# ProDoc_TC264_V2_0_2025-08-21.net
KiCad netlist of a schematic drawn in EasyEDA Pro
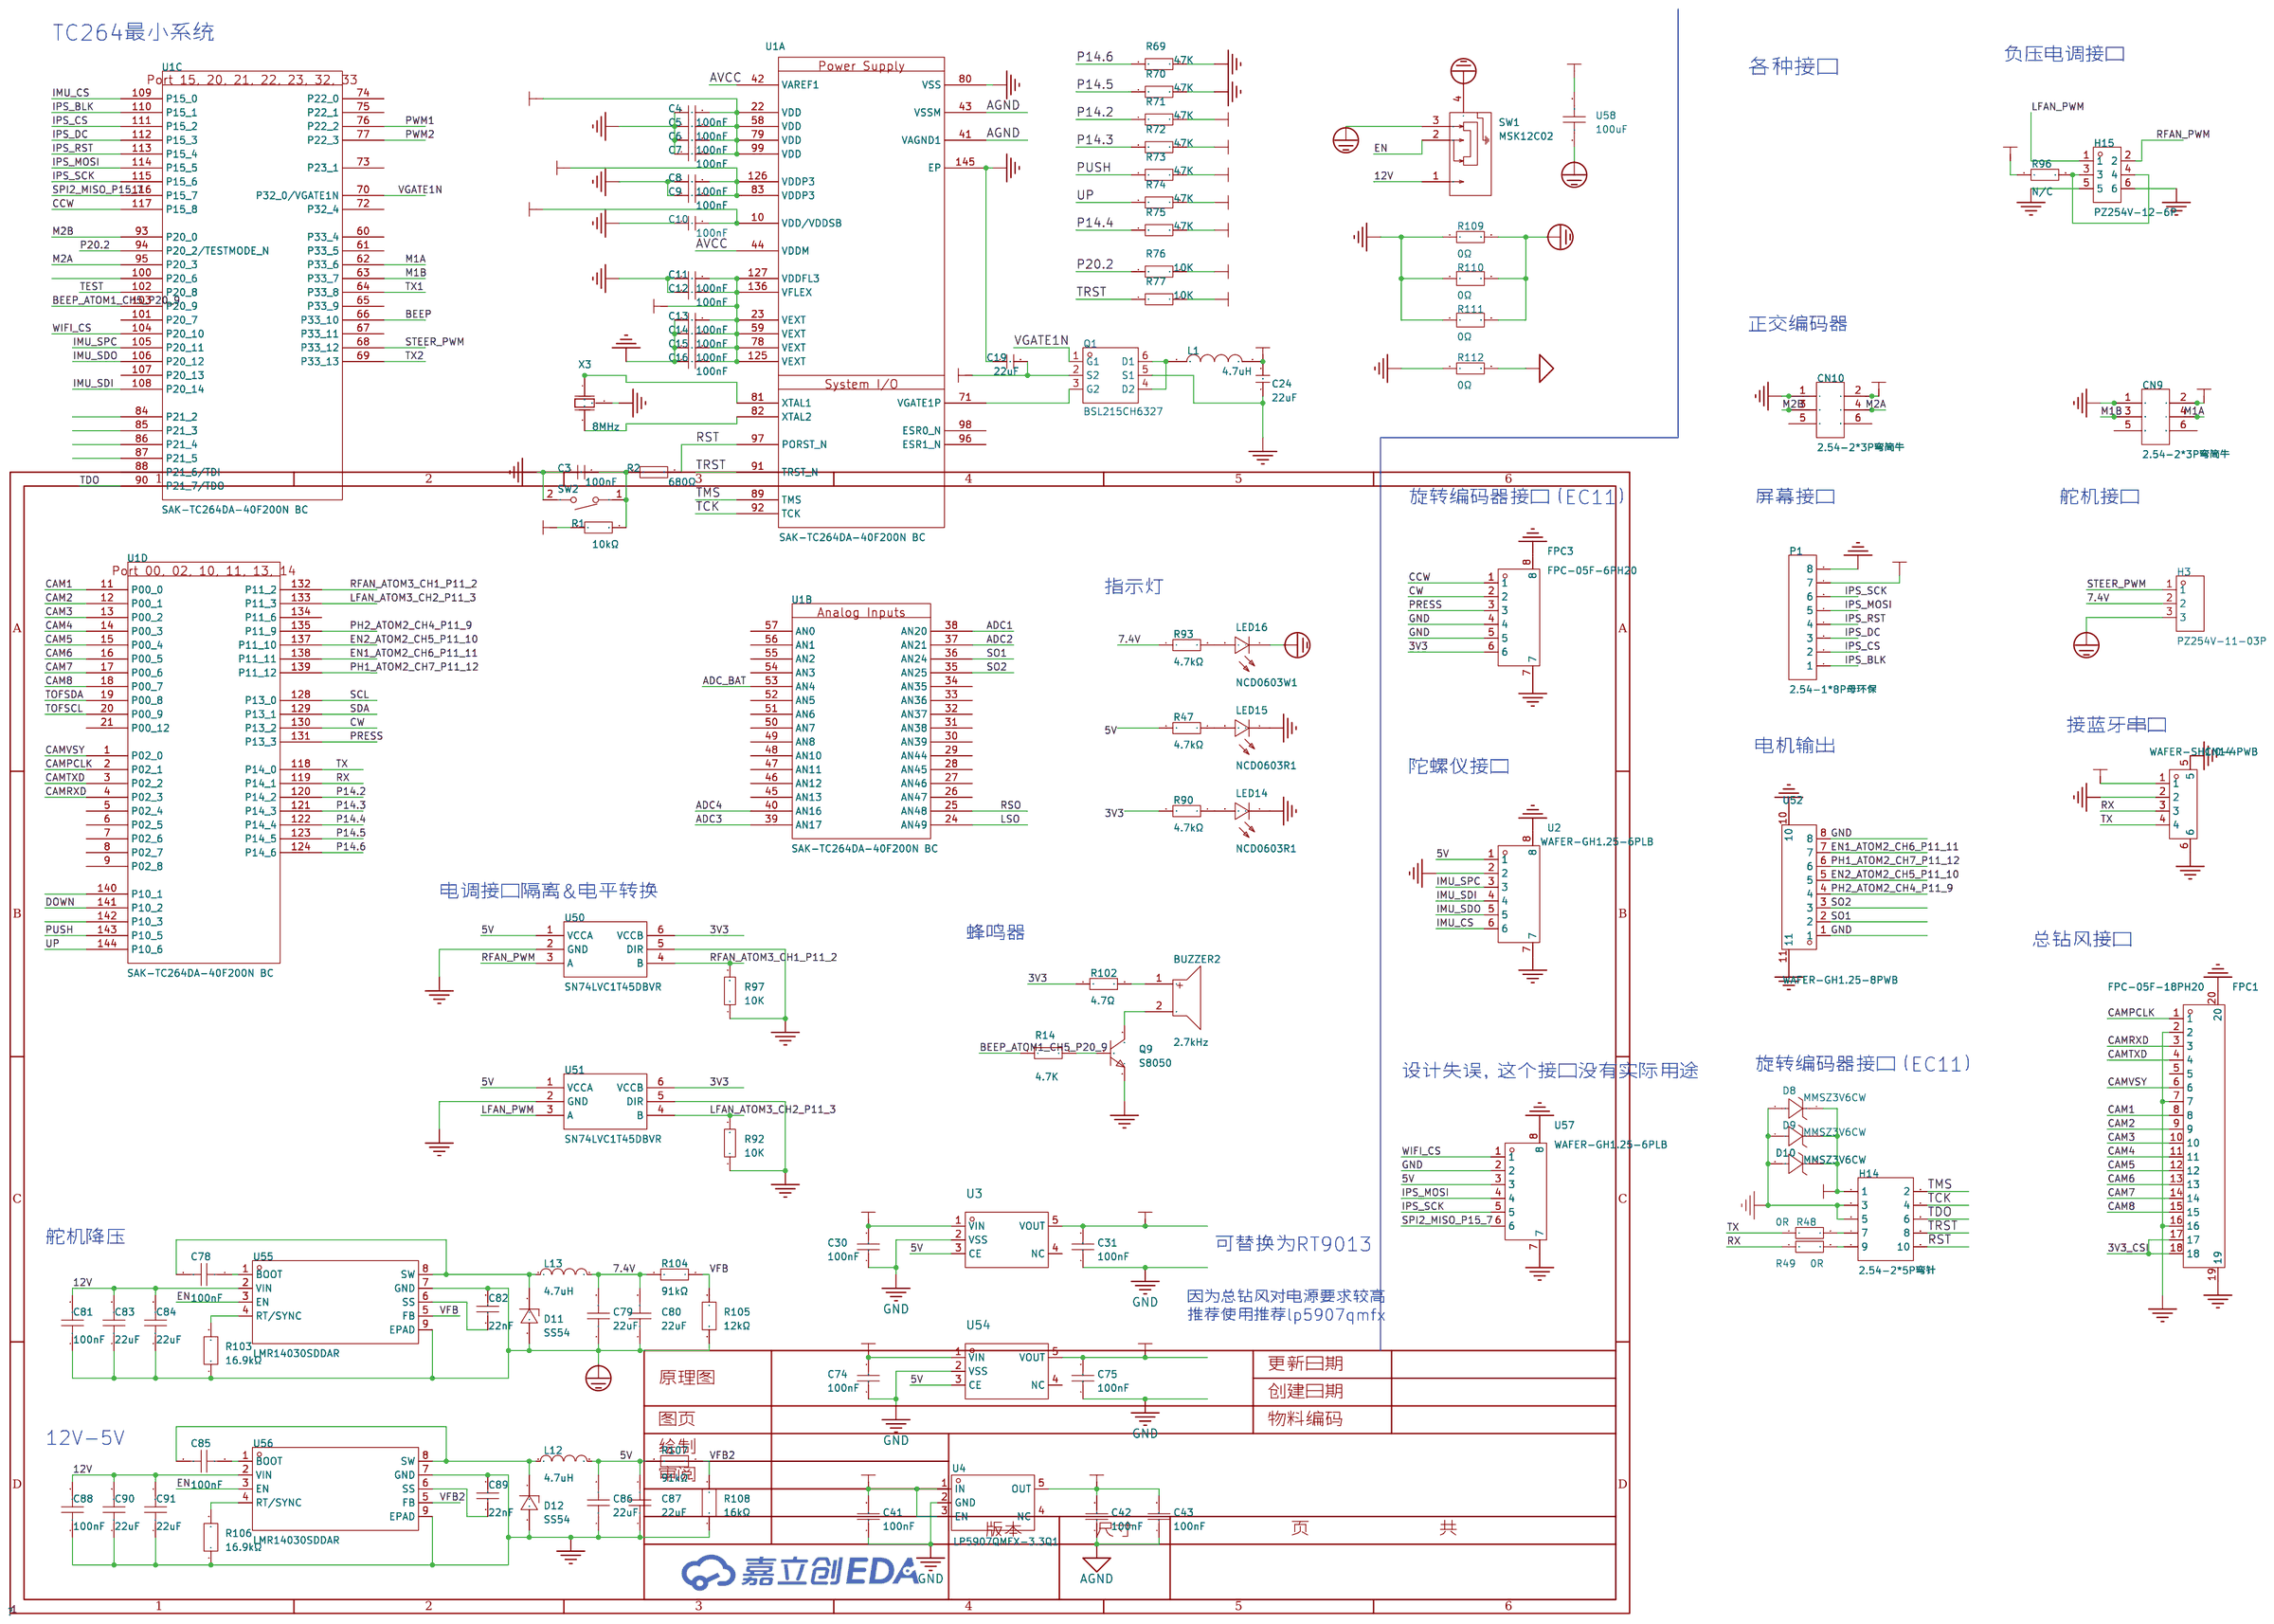
[diagram p0: schematic sheet]

(export (version "E")
  (design (tool "Eeschema 10.0.6"))
  (components
    (comp (ref "BUZZER2")
      (value "2.7kHz")
      (fields (field (name "Manufacturer Part") "QMB-09B-03") (field (name "Manufacturer") "华能"))
      (libsource (lib "easyedapro") (part "QMB-09B-03"))
    )
    (comp (ref "C3")
      (value "100nF")
      (fields (field (name "Manufacturer Part") "0603B104K500NT") (field (name "Manufacturer") "FH(风华)"))
      (libsource (lib "easyedapro") (part "c"))
    )
    (comp (ref "C4")
      (value "100nF")
      (fields (field (name "Manufacturer Part") "0603B104K500NT") (field (name "Manufacturer") "FH(风华)"))
      (libsource (lib "easyedapro") (part "c"))
    )
    (comp (ref "C5")
      (value "100nF")
      (fields (field (name "Manufacturer Part") "0603B104K500NT") (field (name "Manufacturer") "FH(风华)"))
      (libsource (lib "easyedapro") (part "c"))
    )
    (comp (ref "C6")
      (value "100nF")
      (fields (field (name "Manufacturer Part") "0603B104K500NT") (field (name "Manufacturer") "FH(风华)"))
      (libsource (lib "easyedapro") (part "c"))
    )
    (comp (ref "C7")
      (value "100nF")
      (fields (field (name "Manufacturer Part") "0603B104K500NT") (field (name "Manufacturer") "FH(风华)"))
      (libsource (lib "easyedapro") (part "c"))
    )
    (comp (ref "C8")
      (value "100nF")
      (fields (field (name "Manufacturer Part") "0603B104K500NT") (field (name "Manufacturer") "FH(风华)"))
      (libsource (lib "easyedapro") (part "c"))
    )
    (comp (ref "C9")
      (value "100nF")
      (fields (field (name "Manufacturer Part") "0603B104K500NT") (field (name "Manufacturer") "FH(风华)"))
      (libsource (lib "easyedapro") (part "c"))
    )
    (comp (ref "C10")
      (value "100nF")
      (fields (field (name "Manufacturer Part") "0603B104K500NT") (field (name "Manufacturer") "FH(风华)"))
      (libsource (lib "easyedapro") (part "c"))
    )
    (comp (ref "C11")
      (value "100nF")
      (fields (field (name "Manufacturer Part") "0603B104K500NT") (field (name "Manufacturer") "FH(风华)"))
      (libsource (lib "easyedapro") (part "c"))
    )
    (comp (ref "C12")
      (value "100nF")
      (fields (field (name "Manufacturer Part") "0603B104K500NT") (field (name "Manufacturer") "FH(风华)"))
      (libsource (lib "easyedapro") (part "c"))
    )
    (comp (ref "C13")
      (value "100nF")
      (fields (field (name "Manufacturer Part") "0603B104K500NT") (field (name "Manufacturer") "FH(风华)"))
      (libsource (lib "easyedapro") (part "c"))
    )
    (comp (ref "C14")
      (value "100nF")
      (fields (field (name "Manufacturer Part") "0603B104K500NT") (field (name "Manufacturer") "FH(风华)"))
      (libsource (lib "easyedapro") (part "c"))
    )
    (comp (ref "C15")
      (value "100nF")
      (fields (field (name "Manufacturer Part") "0603B104K500NT") (field (name "Manufacturer") "FH(风华)"))
      (libsource (lib "easyedapro") (part "c"))
    )
    (comp (ref "C16")
      (value "100nF")
      (fields (field (name "Manufacturer Part") "0603B104K500NT") (field (name "Manufacturer") "FH(风华)"))
      (libsource (lib "easyedapro") (part "c"))
    )
    (comp (ref "C19")
      (value "22uF")
      (fields
        (field (name "Manufacturer Part") "CL21A226MAQNNNE")
        (field (name "Manufacturer") "SAMSUNG(三星)")
      )
      (libsource (lib "easyedapro") (part "c"))
    )
    (comp (ref "C24")
      (value "22uF")
      (fields
        (field (name "Manufacturer Part") "CL21A226MAQNNNE")
        (field (name "Manufacturer") "SAMSUNG(三星)")
      )
      (libsource (lib "easyedapro") (part "c"))
    )
    (comp (ref "C30")
      (value "100nF")
      (fields (field (name "Manufacturer Part") "0603B104K500NT") (field (name "Manufacturer") "FH(风华)"))
      (libsource (lib "easyedapro") (part "C0603_S"))
    )
    (comp (ref "C31")
      (value "100nF")
      (fields (field (name "Manufacturer Part") "0603B104K500NT") (field (name "Manufacturer") "FH(风华)"))
      (libsource (lib "easyedapro") (part "C0603_S"))
    )
    (comp (ref "C41")
      (value "100nF")
      (fields (field (name "Manufacturer Part") "0603B104K500NT") (field (name "Manufacturer") "FH(风华)"))
      (libsource (lib "easyedapro") (part "C0603_S"))
    )
    (comp (ref "C42")
      (value "100nF")
      (fields (field (name "Manufacturer Part") "0603B104K500NT") (field (name "Manufacturer") "FH(风华)"))
      (libsource (lib "easyedapro") (part "C0603_S"))
    )
    (comp (ref "C43")
      (value "100nF")
      (fields (field (name "Manufacturer Part") "0603B104K500NT") (field (name "Manufacturer") "FH(风华)"))
      (libsource (lib "easyedapro") (part "C0603_S"))
    )
    (comp (ref "C74")
      (value "100nF")
      (fields (field (name "Manufacturer Part") "0603B104K500NT") (field (name "Manufacturer") "FH(风华)"))
      (libsource (lib "easyedapro") (part "C0603_S"))
    )
    (comp (ref "C75")
      (value "100nF")
      (fields (field (name "Manufacturer Part") "0603B104K500NT") (field (name "Manufacturer") "FH(风华)"))
      (libsource (lib "easyedapro") (part "C0603_S"))
    )
    (comp (ref "C78")
      (value "100nF")
      (footprint "easyedapro:C0603")
      (description "容值:100nF;精度:±10%;额定电压:50V;材质(温度系数):X7R;")
      (fields
        (field (name "Manufacturer Part") "CGA0603X7R104K500JT")
        (field (name "Manufacturer") "HRE(芯声)")
      )
      (libsource (lib "easyedapro") (part "CGA0603X7R104K500JT"))
    )
    (comp (ref "C79")
      (value "22uF")
      (footprint "easyedapro:C0805")
      (description "容值:22uF;精度:±20%;额定电压:35V;材质(温度系数):X5R;")
      (fields
        (field (name "Manufacturer Part") "CGA0805X5R226M350MT")
        (field (name "Manufacturer") "HRE(芯声)")
      )
      (libsource (lib "easyedapro") (part "CGA0805X5R226M350MT"))
    )
    (comp (ref "C80")
      (value "22uF")
      (footprint "easyedapro:C0805")
      (description "容值:22uF;精度:±20%;额定电压:35V;材质(温度系数):X5R;")
      (fields
        (field (name "Manufacturer Part") "CGA0805X5R226M350MT")
        (field (name "Manufacturer") "HRE(芯声)")
      )
      (libsource (lib "easyedapro") (part "CGA0805X5R226M350MT"))
    )
    (comp (ref "C81")
      (value "100nF")
      (footprint "easyedapro:C0603")
      (description "容值:100nF;精度:±10%;额定电压:50V;材质(温度系数):X7R;")
      (fields
        (field (name "Manufacturer Part") "CGA0603X7R104K500JT")
        (field (name "Manufacturer") "HRE(芯声)")
      )
      (libsource (lib "easyedapro") (part "CGA0603X7R104K500JT"))
    )
    (comp (ref "C82")
      (value "22nF")
      (footprint "easyedapro:C0603")
      (description "容值:22nF;精度:±10%;额定电压:50V;材质(温度系数):X7R;")
      (fields
        (field (name "Manufacturer Part") "CL10B223KB8NNNC")
        (field (name "Manufacturer") "SAMSUNG(三星)")
      )
      (libsource (lib "easyedapro") (part "CL10B223KB8NNNC"))
    )
    (comp (ref "C83")
      (value "22uF")
      (footprint "easyedapro:C0805")
      (description "容值:22uF;精度:±20%;额定电压:35V;材质(温度系数):X5R;")
      (fields
        (field (name "Manufacturer Part") "CGA0805X5R226M350MT")
        (field (name "Manufacturer") "HRE(芯声)")
      )
      (libsource (lib "easyedapro") (part "CGA0805X5R226M350MT"))
    )
    (comp (ref "C84")
      (value "22uF")
      (footprint "easyedapro:C0805")
      (description "容值:22uF;精度:±20%;额定电压:35V;材质(温度系数):X5R;")
      (fields
        (field (name "Manufacturer Part") "CGA0805X5R226M350MT")
        (field (name "Manufacturer") "HRE(芯声)")
      )
      (libsource (lib "easyedapro") (part "CGA0805X5R226M350MT"))
    )
    (comp (ref "C85")
      (value "100nF")
      (footprint "easyedapro:C0603")
      (description "容值:100nF;精度:±10%;额定电压:50V;材质(温度系数):X7R;")
      (fields
        (field (name "Manufacturer Part") "CGA0603X7R104K500JT")
        (field (name "Manufacturer") "HRE(芯声)")
      )
      (libsource (lib "easyedapro") (part "CGA0603X7R104K500JT"))
    )
    (comp (ref "C86")
      (value "22uF")
      (footprint "easyedapro:C0805")
      (description "容值:22uF;精度:±20%;额定电压:35V;材质(温度系数):X5R;")
      (fields
        (field (name "Manufacturer Part") "CGA0805X5R226M350MT")
        (field (name "Manufacturer") "HRE(芯声)")
      )
      (libsource (lib "easyedapro") (part "CGA0805X5R226M350MT"))
    )
    (comp (ref "C87")
      (value "22uF")
      (footprint "easyedapro:C0805")
      (description "容值:22uF;精度:±20%;额定电压:35V;材质(温度系数):X5R;")
      (fields
        (field (name "Manufacturer Part") "CGA0805X5R226M350MT")
        (field (name "Manufacturer") "HRE(芯声)")
      )
      (libsource (lib "easyedapro") (part "CGA0805X5R226M350MT"))
    )
    (comp (ref "C88")
      (value "100nF")
      (footprint "easyedapro:C0603")
      (description "容值:100nF;精度:±10%;额定电压:50V;材质(温度系数):X7R;")
      (fields
        (field (name "Manufacturer Part") "CGA0603X7R104K500JT")
        (field (name "Manufacturer") "HRE(芯声)")
      )
      (libsource (lib "easyedapro") (part "CGA0603X7R104K500JT"))
    )
    (comp (ref "C89")
      (value "22nF")
      (footprint "easyedapro:C0603")
      (description "容值:22nF;精度:±10%;额定电压:50V;材质(温度系数):X7R;")
      (fields
        (field (name "Manufacturer Part") "CL10B223KB8NNNC")
        (field (name "Manufacturer") "SAMSUNG(三星)")
      )
      (libsource (lib "easyedapro") (part "CL10B223KB8NNNC"))
    )
    (comp (ref "C90")
      (value "22uF")
      (footprint "easyedapro:C0805")
      (description "容值:22uF;精度:±20%;额定电压:35V;材质(温度系数):X5R;")
      (fields
        (field (name "Manufacturer Part") "CGA0805X5R226M350MT")
        (field (name "Manufacturer") "HRE(芯声)")
      )
      (libsource (lib "easyedapro") (part "CGA0805X5R226M350MT"))
    )
    (comp (ref "C91")
      (value "22uF")
      (footprint "easyedapro:C0805")
      (description "容值:22uF;精度:±20%;额定电压:35V;材质(温度系数):X5R;")
      (fields
        (field (name "Manufacturer Part") "CGA0805X5R226M350MT")
        (field (name "Manufacturer") "HRE(芯声)")
      )
      (libsource (lib "easyedapro") (part "CGA0805X5R226M350MT"))
    )
    (comp (ref "CN9")
      (value "2.54-2*3P弯简牛")
      (footprint "easyedapro:IDC-TH_6P-P2.54-H-R2-C3-S2.54")
      (description "连接器类型:简牛座;间距:2.54mm;结构:2x3P;封装形式:弯插;行距:2.54mm;排数:2;每排PIN数:3;触头材质:-;触头镀层:-;")
      (fields (field (name "Manufacturer") "BOOMELE(博穆精密)"))
      (libsource (lib "easyedapro") (part "2.54mm 2*3P bend IDC Box"))
    )
    (comp (ref "CN10")
      (value "2.54-2*3P弯简牛")
      (footprint "easyedapro:IDC-TH_6P-P2.54-H-R2-C3-S2.54")
      (description "连接器类型:简牛座;间距:2.54mm;结构:2x3P;封装形式:弯插;行距:2.54mm;排数:2;每排PIN数:3;触头材质:-;触头镀层:-;")
      (fields (field (name "Manufacturer") "BOOMELE(博穆精密)"))
      (libsource (lib "easyedapro") (part "2.54mm 2*3P bend IDC Box"))
    )
    (comp (ref "CN14")
      (value "WAFER-SH1.0-4PWB")
      (footprint "easyedapro:CONN-SMD_4P-P1.00_WAFER-SH1.0-4PWB")
      (fields (field (name "Manufacturer") "XUNPU(讯普)"))
      (libsource (lib "easyedapro") (part "WAFER-SH1.0-4PWB"))
    )
    (comp (ref "D8")
      (value "MMSZ3V6CW")
      (footprint "easyedapro:SOD-123_L2.7-W1.6-LS3.7-RD-1")
      (description "二极管配置:独立式;稳压值(标称值):3.6V;稳压值(范围):3.4V~3.8V;功率(Pd):500mW;")
      (fields (field (name "Manufacturer") "YONGYUTAI(永裕泰)"))
      (libsource (lib "easyedapro") (part "MMSZ3V6CW_C2922768"))
    )
    (comp (ref "D9")
      (value "MMSZ3V6CW")
      (footprint "easyedapro:SOD-123_L2.7-W1.6-LS3.7-RD-1")
      (description "二极管配置:独立式;稳压值(标称值):3.6V;稳压值(范围):3.4V~3.8V;功率(Pd):500mW;")
      (fields (field (name "Manufacturer") "YONGYUTAI(永裕泰)"))
      (libsource (lib "easyedapro") (part "MMSZ3V6CW_C2922768"))
    )
    (comp (ref "D10")
      (value "MMSZ3V6CW")
      (footprint "easyedapro:SOD-123_L2.7-W1.6-LS3.7-RD-1")
      (description "二极管配置:独立式;稳压值(标称值):3.6V;稳压值(范围):3.4V~3.8V;功率(Pd):500mW;")
      (fields (field (name "Manufacturer") "YONGYUTAI(永裕泰)"))
      (libsource (lib "easyedapro") (part "MMSZ3V6CW_C2922768"))
    )
    (comp (ref "D11")
      (value "SS54")
      (footprint "easyedapro:SMA_L4.3-W2.6-LS5.0-FD")
      (description "二极管配置:独立式;正向压降(Vf):550mV@5.0A;直流反向耐压(Vr):40V;整流电流:5A;")
      (fields (field (name "Manufacturer") "宏迦橙"))
      (libsource (lib "easyedapro") (part "SS54_C7420369"))
    )
    (comp (ref "D12")
      (value "SS54")
      (footprint "easyedapro:SMA_L4.3-W2.6-LS5.0-FD")
      (description "二极管配置:独立式;正向压降(Vf):550mV@5.0A;直流反向耐压(Vr):40V;整流电流:5A;")
      (fields (field (name "Manufacturer") "宏迦橙"))
      (libsource (lib "easyedapro") (part "SS54_C7420369"))
    )
    (comp (ref "FPC1")
      (value "FPC-05F-18PH20")
      (footprint "easyedapro:FPC-SMD_18P-P0.50_FPC-05F-18PH20")
      (description "锁定特性:翻盖式;触点类型:下接;触点数量:18P;间距:0.5mm;安装类型:卧贴;工作温度范围:-25°C~+85°C;")
      (fields (field (name "Manufacturer") "XUNPU(讯普)"))
      (libsource (lib "easyedapro") (part "FPC-05F-18PH20"))
    )
    (comp (ref "FPC3")
      (value "FPC-05F-6PH20")
      (footprint "easyedapro:FPC-SMD_6P-P0.50_XUNPU_FPC-05F-6PH20")
      (description "锁定特性:翻盖式;触点类型:下接;触点数量:6P;间距:0.5mm;安装类型:卧贴;工作温度范围:-25°C~+85°C;")
      (fields (field (name "Manufacturer") "XUNPU(讯普)"))
      (libsource (lib "easyedapro") (part "FPC-05F-6PH20"))
    )
    (comp (ref "H3")
      (value "PZ254V-11-03P")
      (fields (field (name "Manufacturer") "XFCN(兴飞)"))
      (libsource (lib "easyedapro") (part "PZ254V-11-03P_C2937625"))
    )
    (comp (ref "H14")
      (value "2.54-2*5P弯针")
      (footprint "easyedapro:HDR-TH_10P-P2.54-H-M-R2-C5-S2.54-W12.9")
      (fields (field (name "Manufacturer") "BOOMELE(博穆精密)"))
      (libsource (lib "easyedapro") (part "2*5P header"))
    )
    (comp (ref "H15")
      (value "PZ254V-12-6P")
      (footprint "easyedapro:HDR-TH_6P-P2.54-V-M-R2-C3-S2.54")
      (fields (field (name "Manufacturer") "XFCN(兴飞)"))
      (libsource (lib "easyedapro") (part "PZ254V-12-6P"))
    )
    (comp (ref "L1")
      (value "4.7uH")
      (fields (field (name "Manufacturer Part") "LQM21PL4R7MGCD") (field (name "Manufacturer") "muRata(村田)"))
      (libsource (lib "easyedapro") (part "l"))
    )
    (comp (ref "L12")
      (value "4.7uH")
      (footprint "easyedapro:IND-SMD_L7.0-W6.6")
      (description "电感值:4.7uH;精度:±20%;额定电流:6A;饱和电流(Isat):9A;类型:一体成型电感;")
      (fields (field (name "Manufacturer Part") "FXL0630-4R7-M") (field (name "Manufacturer") "cjiang(长江微电)"))
      (libsource (lib "easyedapro") (part "FXL0630-4R7-M"))
    )
    (comp (ref "L13")
      (value "4.7uH")
      (footprint "easyedapro:IND-SMD_L7.0-W6.6")
      (description "电感值:4.7uH;精度:±20%;额定电流:6A;饱和电流(Isat):9A;类型:一体成型电感;")
      (fields (field (name "Manufacturer Part") "FXL0630-4R7-M") (field (name "Manufacturer") "cjiang(长江微电)"))
      (libsource (lib "easyedapro") (part "FXL0630-4R7-M"))
    )
    (comp (ref "LED14")
      (value "NCD0603R1")
      (footprint "easyedapro:LED0603-RD_RED")
      (fields (field (name "Manufacturer") "国星光电"))
      (libsource (lib "easyedapro") (part "FC-DA1608HRK-620D"))
    )
    (comp (ref "LED15")
      (value "NCD0603R1")
      (footprint "easyedapro:LED0603-RD_RED")
      (fields (field (name "Manufacturer") "国星光电"))
      (libsource (lib "easyedapro") (part "FC-DA1608HRK-620D"))
    )
    (comp (ref "LED16")
      (value "NCD0603W1")
      (footprint "easyedapro:LED0603-RD")
      (fields (field (name "Manufacturer") "国星光电"))
      (libsource (lib "easyedapro") (part "NCD0603W1"))
    )
    (comp (ref "P1")
      (value "2.54-1*8P母环保")
      (footprint "easyedapro:HDR-TH_8P-P2.54-V-F-1")
      (description "插孔结构:1x8P;间距:2.54mm;行距:-;安装类型:直插;排数:单排;总孔位数:8P;塑高:-;触头材质:-;触头镀层:-;")
      (fields (field (name "Manufacturer") "BOOMELE(博穆精密)"))
      (libsource (lib "easyedapro") (part "Header-Female-2.54_1x8"))
    )
    (comp (ref "Q1")
      (value "BSL215CH6327")
      (fields (field (name "Manufacturer") "Infineon(英飞凌)"))
      (libsource (lib "easyedapro") (part "bsl215ch6327xtsa1"))
    )
    (comp (ref "Q9")
      (value "S8050")
      (footprint "easyedapro:SOT-23-3_L2.9-W1.3-P1.90-LS2.4-BR")
      (description "晶体管类型:NPN;集电极电流(Ic):500mA;集射极击穿电压(Vceo):25V;功率(Pd):300mW;")
      (fields (field (name "Manufacturer") "YONGYUTAI(永裕泰)"))
      (libsource (lib "easyedapro") (part "S8050_C2891804"))
    )
    (comp (ref "R1")
      (value "10kΩ")
      (fields
        (field (name "Manufacturer Part") "0603WAF1002T5E")
        (field (name "Manufacturer") "UNI-ROYAL(厚声)")
      )
      (libsource (lib "easyedapro") (part "r"))
    )
    (comp (ref "R2")
      (value "680Ω")
      (fields
        (field (name "Manufacturer Part") "0603WAF6800T5E")
        (field (name "Manufacturer") "UNI-ROYAL(厚声)")
      )
      (libsource (lib "easyedapro") (part "r"))
    )
    (comp (ref "R14") (value "4.7K") (libsource (lib "easyedapro") (part "电阻")))
    (comp (ref "R47")
      (value "4.7kΩ")
      (footprint "easyedapro:R0603")
      (description "电阻类型:厚膜电阻;阻值:4.7kΩ;精度:±1%;功率:100mW;最大工作电压:75V;温度系数:±100ppm/°C;")
      (fields (field (name "Manufacturer Part") "RC0603FR-074K7L") (field (name "Manufacturer") "YAGEO(国巨)"))
      (libsource (lib "easyedapro") (part "RC0603FR-074K7L"))
    )
    (comp (ref "R48") (value "0R") (libsource (lib "easyedapro") (part "电阻")))
    (comp (ref "R49") (value "0R") (libsource (lib "easyedapro") (part "电阻")))
    (comp (ref "R69") (value "47K") (libsource (lib "easyedapro") (part "电阻")))
    (comp (ref "R70") (value "47K") (libsource (lib "easyedapro") (part "电阻")))
    (comp (ref "R71") (value "47K") (libsource (lib "easyedapro") (part "电阻")))
    (comp (ref "R72") (value "47K") (libsource (lib "easyedapro") (part "电阻")))
    (comp (ref "R73") (value "47K") (libsource (lib "easyedapro") (part "电阻")))
    (comp (ref "R74") (value "47K") (libsource (lib "easyedapro") (part "电阻")))
    (comp (ref "R75") (value "47K") (libsource (lib "easyedapro") (part "电阻")))
    (comp (ref "R76") (value "10K") (libsource (lib "easyedapro") (part "电阻")))
    (comp (ref "R77") (value "10K") (libsource (lib "easyedapro") (part "电阻")))
    (comp (ref "R90")
      (value "4.7kΩ")
      (footprint "easyedapro:R0603")
      (description "电阻类型:厚膜电阻;阻值:4.7kΩ;精度:±1%;功率:100mW;最大工作电压:75V;温度系数:±100ppm/°C;")
      (fields (field (name "Manufacturer Part") "RC0603FR-074K7L") (field (name "Manufacturer") "YAGEO(国巨)"))
      (libsource (lib "easyedapro") (part "RC0603FR-074K7L"))
    )
    (comp (ref "R92") (value "10K") (footprint "easyedapro:R0603") (libsource (lib "easyedapro") (part "电阻")))
    (comp (ref "R93")
      (value "4.7kΩ")
      (footprint "easyedapro:R0603")
      (description "电阻类型:厚膜电阻;阻值:6.8kΩ;精度:±1%;功率:100mW;最大工作电压:75V;温度系数:±100ppm/°C;")
      (fields
        (field (name "Manufacturer Part") "0603WAF6801T5E")
        (field (name "Manufacturer") "UNI-ROYAL(厚声)")
      )
      (libsource (lib "easyedapro") (part "0603WAF6801T5E"))
    )
    (comp (ref "R96")
      (value "N/C")
      (footprint "easyedapro:R0603")
      (description "电阻类型:厚膜电阻;阻值:0Ω;精度:±1%;功率:100mW;最大工作电压:75V;")
      (fields
        (field (name "Manufacturer Part") "0603WAF0000T5E")
        (field (name "Manufacturer") "UNI-ROYAL(厚声)")
      )
      (libsource (lib "easyedapro") (part "0603WAF0000T5E"))
    )
    (comp (ref "R97") (value "10K") (footprint "easyedapro:R0603") (libsource (lib "easyedapro") (part "电阻")))
    (comp (ref "R102")
      (value "4.7Ω")
      (footprint "easyedapro:R0603")
      (description "电阻类型:厚膜电阻;阻值:100Ω;精度:±1%;功率:100mW;最大工作电压:75V;温度系数:±200ppm/°C;")
      (fields
        (field (name "Manufacturer Part") "0603WAF1000T5E")
        (field (name "Manufacturer") "UNI-ROYAL(厚声)")
      )
      (libsource (lib "easyedapro") (part "0603WAF1000T5E"))
    )
    (comp (ref "R103")
      (value "16.9kΩ")
      (footprint "easyedapro:R0603")
      (description "电阻类型:薄膜电阻;阻值:16.9kΩ;精度:±0.1%;功率:100mW;温度系数:±25ppm/°C;")
      (fields (field (name "Manufacturer Part") "RT0603BRD0716K9L") (field (name "Manufacturer") "YAGEO(国巨)"))
      (libsource (lib "easyedapro") (part "RT0603BRD0716K9L"))
    )
    (comp (ref "R104")
      (value "91kΩ")
      (footprint "easyedapro:R0603")
      (description "电阻类型:厚膜电阻;阻值:100kΩ;精度:±1%;功率:100mW;最大工作电压:75V;温度系数:±100ppm/°C;")
      (fields
        (field (name "Manufacturer Part") "0603WAF1003T5E")
        (field (name "Manufacturer") "UNI-ROYAL(厚声)")
      )
      (libsource (lib "easyedapro") (part "0603WAF1003T5E"))
    )
    (comp (ref "R105")
      (value "12kΩ")
      (footprint "easyedapro:R0603")
      (description "电阻类型:薄膜电阻;阻值:17.8kΩ;精度:±0.1%;功率:100mW;最大工作电压:75V;温度系数:±25ppm/°C;")
      (fields (field (name "Manufacturer Part") "RT0603BRD0717K8L") (field (name "Manufacturer") "YAGEO(国巨)"))
      (libsource (lib "easyedapro") (part "RT0603BRD0717K8L"))
    )
    (comp (ref "R106")
      (value "16.9kΩ")
      (footprint "easyedapro:R0603")
      (description "电阻类型:薄膜电阻;阻值:16.9kΩ;精度:±0.1%;功率:100mW;温度系数:±25ppm/°C;")
      (fields (field (name "Manufacturer Part") "RT0603BRD0716K9L") (field (name "Manufacturer") "YAGEO(国巨)"))
      (libsource (lib "easyedapro") (part "RT0603BRD0716K9L"))
    )
    (comp (ref "R107")
      (value "91kΩ")
      (footprint "easyedapro:R0603")
      (description "电阻类型:厚膜电阻;阻值:100kΩ;精度:±1%;功率:100mW;最大工作电压:75V;温度系数:±100ppm/°C;")
      (fields
        (field (name "Manufacturer Part") "0603WAF1003T5E")
        (field (name "Manufacturer") "UNI-ROYAL(厚声)")
      )
      (libsource (lib "easyedapro") (part "0603WAF1003T5E"))
    )
    (comp (ref "R108")
      (value "16kΩ")
      (footprint "easyedapro:R0603")
      (description "电阻类型:薄膜电阻;阻值:17.8kΩ;精度:±0.1%;功率:100mW;最大工作电压:75V;温度系数:±25ppm/°C;")
      (fields (field (name "Manufacturer Part") "RT0603BRD0717K8L") (field (name "Manufacturer") "YAGEO(国巨)"))
      (libsource (lib "easyedapro") (part "RT0603BRD0717K8L"))
    )
    (comp (ref "R109")
      (value "0Ω")
      (footprint "easyedapro:R1206")
      (description "电阻类型:厚膜电阻;阻值:0Ω;精度:±1%;功率:250mW;最大工作电压:200V;温度系数:±800ppm/°C;")
      (fields
        (field (name "Manufacturer Part") "1206W4F0000T5E")
        (field (name "Manufacturer") "UNI-ROYAL(厚声)")
      )
      (libsource (lib "easyedapro") (part "1206W4F0000T5E"))
    )
    (comp (ref "R110")
      (value "0Ω")
      (footprint "easyedapro:R1206")
      (description "电阻类型:厚膜电阻;阻值:0Ω;精度:±5%;功率:250mW;最大工作电压:200V;")
      (fields (field (name "Manufacturer Part") "FRC1206P000 TS") (field (name "Manufacturer") "FOJAN(富捷)"))
      (libsource (lib "easyedapro") (part "FRC1206P000 TS"))
    )
    (comp (ref "R111")
      (value "0Ω")
      (footprint "easyedapro:R1206")
      (description "电阻类型:厚膜电阻;阻值:0Ω;精度:±5%;功率:250mW;最大工作电压:200V;")
      (fields (field (name "Manufacturer Part") "FRC1206P000 TS") (field (name "Manufacturer") "FOJAN(富捷)"))
      (libsource (lib "easyedapro") (part "FRC1206P000 TS"))
    )
    (comp (ref "R112")
      (value "0Ω")
      (footprint "easyedapro:R0603")
      (description "电阻类型:厚膜电阻;阻值:0Ω;精度:±1%;功率:100mW;最大工作电压:75V;")
      (fields
        (field (name "Manufacturer Part") "0603WAF0000T5E")
        (field (name "Manufacturer") "UNI-ROYAL(厚声)")
      )
      (libsource (lib "easyedapro") (part "0603WAF0000T5E"))
    )
    (comp (ref "SW1")
      (value "MSK12C02")
      (footprint "easyedapro:SW-TH_MSK12C02")
      (description "电路结构:单刀双掷;安装方式:卧贴;开关颜色:-;额定电流(DC):50mA;额定电压(DC):12V;额定电流(AC):-;额定电压(AC):-;机械寿命:1万次;")
      (fields (field (name "Manufacturer") "SHOU HAN(首韩)"))
      (libsource (lib "easyedapro") (part "MSK12C02"))
    )
    (comp (ref "SW2")
      (value "TS-1063S-B3D4")
      (footprint "easyedapro:KEY-SMD_L3.0-W2.5-LS4.0_TS-1603S")
      (description "电路结构:单刀单掷;安装方式:-;按钮形状:方形按钮;带灯:-;作用力:250gf@±30gf;")
      (fields (field (name "Manufacturer") "Yuandi(元迪)"))
      (libsource (lib "easyedapro") (part "TS-1063S-B3D4"))
    )
    (comp (ref "U1")
      (value "SAK-TC264DA-40F200N BC")
      (description "32-Bit Single-Chip Microcontroller BC-Step")
      (libsource (lib "easyedapro") (part "sak-tc264da-40f200n bc"))
    )
    (comp (ref "U2")
      (value "WAFER-GH1.25-6PLB")
      (footprint "easyedapro:CONN-SMD_6P-P1.25_XUNPU_WAFER-GH1.25-6PLB")
      (fields (field (name "Manufacturer") "XUNPU(讯普)"))
      (libsource (lib "easyedapro") (part "WAFER-GH1.25-6PLB"))
    )
    (comp (ref "U3") (value "XC6210B332MR") (libsource (lib "easyedapro") (part "XC6210B332MR")))
    (comp (ref "U4")
      (value "LP5907QMFX-3.3Q1")
      (fields (field (name "Manufacturer") "TI(德州仪器)"))
      (libsource (lib "easyedapro") (part "LP5907QMFX-3.3Q1"))
    )
    (comp (ref "U50")
      (value "SN74LVC1T45DBVR")
      (footprint "easyedapro:SOT-23-6_L2.9-W1.6-P0.95-LS2.8-BR")
      (description "数据速率:420Mbps;电压(VCCA):1.65V~5.5V;电压(VCCB):1.65V~5.5V;电路数:1;每个电路通道数:1;")
      (fields (field (name "Manufacturer") "TI(德州仪器)"))
      (libsource (lib "easyedapro") (part "SN74LVC1T45DBVR"))
    )
    (comp (ref "U51")
      (value "SN74LVC1T45DBVR")
      (footprint "easyedapro:SOT-23-6_L2.9-W1.6-P0.95-LS2.8-BR")
      (description "数据速率:420Mbps;电压(VCCA):1.65V~5.5V;电压(VCCB):1.65V~5.5V;电路数:1;每个电路通道数:1;")
      (fields (field (name "Manufacturer") "TI(德州仪器)"))
      (libsource (lib "easyedapro") (part "SN74LVC1T45DBVR"))
    )
    (comp (ref "U52")
      (value "WAFER-GH1.25-8PWB")
      (footprint "easyedapro:CONN-SMD_8P-P1.25_XUNPU-WAFER-GH1.25-8PWB")
      (description "插针结构:1x8P;间距:1.25mm;安装方式:卧贴;参考系列:GH;总PIN数:8P;排数:1;每排PIN数:8;额定电流:1A;工作温度范围:-25°C~+85°C;")
      (fields (field (name "Manufacturer") "XUNPU(讯普)"))
      (libsource (lib "easyedapro") (part "WAFER-GH1.25-8PWB"))
    )
    (comp (ref "U54") (value "XC6210B332MR") (libsource (lib "easyedapro") (part "XC6210B332MR")))
    (comp (ref "U55")
      (value "LMR14030SDDAR")
      (footprint "easyedapro:SO-8_L4.9-W3.9-P1.27-LS6.0-BL-EP")
      (description "功能类型:降压型;输出类型:可调;输入电压:4V~40V;输出电压:800mV~28V;输出电流(最大值):3.5A;")
      (fields (field (name "Manufacturer") "TI(德州仪器)"))
      (libsource (lib "easyedapro") (part "LMR14030SDDAR"))
    )
    (comp (ref "U56")
      (value "LMR14030SDDAR")
      (footprint "easyedapro:SO-8_L4.9-W3.9-P1.27-LS6.0-BL-EP")
      (description "功能类型:降压型;输出类型:可调;输入电压:4V~40V;输出电压:800mV~28V;输出电流(最大值):3.5A;")
      (fields (field (name "Manufacturer") "TI(德州仪器)"))
      (libsource (lib "easyedapro") (part "LMR14030SDDAR"))
    )
    (comp (ref "U57")
      (value "WAFER-GH1.25-6PLB")
      (footprint "easyedapro:CONN-SMD_6P-P1.25_XUNPU_WAFER-GH1.25-6PLB")
      (fields (field (name "Manufacturer") "XUNPU(讯普)"))
      (libsource (lib "easyedapro") (part "WAFER-GH1.25-6PLB"))
    )
    (comp (ref "U58")
      (value "100uF")
      (footprint "easyedapro:C1210")
      (description "容值:100uF;精度:±20%;额定电压:16V;材质(温度系数):X5R;")
      (fields
        (field (name "Manufacturer Part") "HGC1210R5107M160NSVK")
        (field (name "Manufacturer") "Chinocera(华瓷)")
      )
      (libsource (lib "easyedapro") (part "HGC1210R5107M160NSVK"))
    )
    (comp (ref "X3")
      (value "8MHz")
      (footprint "easyedapro:OSC-SMD_3P-L3.2-W1.3-P1.20-L")
      (description "频率:8MHz;内置负载电容:33pF;谐振阻抗:40Ω;")
      (fields
        (field (name "Manufacturer Part") "CSTNE8M00GH5C000R0")
        (field (name "Manufacturer") "muRata(村田)")
      )
      (libsource (lib "easyedapro") (part "CSTNE8M00GH5C000R0"))
    )
  )
  (nets
    (net (code "1") (name "/7.4V") (class "Default")
      (node (ref "C79") (pin "2") (pinfunction "2_2") (pintype "unspecified"))
      (node (ref "C80") (pin "2") (pinfunction "2_2") (pintype "unspecified"))
      (node (ref "H3") (pin "2") (pinfunction "2_2") (pintype "unspecified"))
      (node (ref "L13") (pin "2") (pinfunction "2_2") (pintype "unspecified"))
      (node (ref "R104") (pin "2") (pinfunction "2_2") (pintype "input"))
      (node (ref "R93") (pin "1") (pinfunction "1_1") (pintype "input"))
    )
    (net (code "2") (name "/ADC1") (class "Default")
      (node (ref "U1") (pin "38") (pinfunction "AN20_38") (pintype "input"))
    )
    (net (code "3") (name "/ADC2") (class "Default")
      (node (ref "U1") (pin "37") (pinfunction "AN21_37") (pintype "input"))
    )
    (net (code "4") (name "/ADC3") (class "Default")
      (node (ref "U1") (pin "39") (pinfunction "AN17_39") (pintype "input"))
    )
    (net (code "5") (name "/ADC4") (class "Default")
      (node (ref "U1") (pin "40") (pinfunction "AN16_40") (pintype "input"))
    )
    (net (code "6") (name "/ADC_BAT") (class "Default")
      (node (ref "U1") (pin "53") (pinfunction "AN4_53") (pintype "input"))
    )
    (net (code "7") (name "/BEEP") (class "Default")
      (node (ref "U1") (pin "66") (pinfunction "P33_10_66") (pintype "bidirectional"))
    )
    (net (code "8") (name "/BEEP_ATOM1_CH5_P20_9") (class "Default")
      (node (ref "R14") (pin "1") (pinfunction "1_1") (pintype "input"))
      (node (ref "U1") (pin "103") (pinfunction "P20_9_103") (pintype "bidirectional"))
    )
    (net (code "9") (name "/CAM1") (class "Default")
      (node (ref "FPC1") (pin "8") (pinfunction "8_8") (pintype "unspecified"))
      (node (ref "U1") (pin "11") (pinfunction "P00_0_11") (pintype "bidirectional"))
    )
    (net (code "10") (name "/CAM2") (class "Default")
      (node (ref "FPC1") (pin "9") (pinfunction "9_9") (pintype "unspecified"))
      (node (ref "U1") (pin "12") (pinfunction "P00_1_12") (pintype "bidirectional"))
    )
    (net (code "11") (name "/CAM3") (class "Default")
      (node (ref "FPC1") (pin "10") (pinfunction "10_10") (pintype "unspecified"))
      (node (ref "U1") (pin "13") (pinfunction "P00_2_13") (pintype "bidirectional"))
    )
    (net (code "12") (name "/CAM4") (class "Default")
      (node (ref "FPC1") (pin "11") (pinfunction "11_11") (pintype "unspecified"))
      (node (ref "U1") (pin "14") (pinfunction "P00_3_14") (pintype "bidirectional"))
    )
    (net (code "13") (name "/CAM5") (class "Default")
      (node (ref "FPC1") (pin "12") (pinfunction "12_12") (pintype "unspecified"))
      (node (ref "U1") (pin "15") (pinfunction "P00_4_15") (pintype "bidirectional"))
    )
    (net (code "14") (name "/CAM6") (class "Default")
      (node (ref "FPC1") (pin "13") (pinfunction "13_13") (pintype "unspecified"))
      (node (ref "U1") (pin "16") (pinfunction "P00_5_16") (pintype "bidirectional"))
    )
    (net (code "15") (name "/CAM7") (class "Default")
      (node (ref "FPC1") (pin "14") (pinfunction "14_14") (pintype "unspecified"))
      (node (ref "U1") (pin "17") (pinfunction "P00_6_17") (pintype "bidirectional"))
    )
    (net (code "16") (name "/CAM8") (class "Default")
      (node (ref "FPC1") (pin "15") (pinfunction "15_15") (pintype "unspecified"))
      (node (ref "U1") (pin "18") (pinfunction "P00_7_18") (pintype "bidirectional"))
    )
    (net (code "17") (name "/CAMPCLK") (class "Default")
      (node (ref "FPC1") (pin "1") (pinfunction "1_1") (pintype "unspecified"))
      (node (ref "U1") (pin "2") (pinfunction "P02_1_2") (pintype "bidirectional"))
    )
    (net (code "18") (name "/CAMRXD") (class "Default")
      (node (ref "FPC1") (pin "3") (pinfunction "3_3") (pintype "unspecified"))
      (node (ref "U1") (pin "4") (pinfunction "P02_3_4") (pintype "bidirectional"))
    )
    (net (code "19") (name "/CAMTXD") (class "Default")
      (node (ref "FPC1") (pin "4") (pinfunction "4_4") (pintype "unspecified"))
      (node (ref "U1") (pin "3") (pinfunction "P02_2_3") (pintype "bidirectional"))
    )
    (net (code "20") (name "/CAMVSY") (class "Default")
      (node (ref "FPC1") (pin "6") (pinfunction "6_6") (pintype "unspecified"))
      (node (ref "U1") (pin "1") (pinfunction "P02_0_1") (pintype "bidirectional"))
    )
    (net (code "21") (name "/CCW") (class "Default")
      (node (ref "FPC3") (pin "1") (pinfunction "1_1") (pintype "unspecified"))
      (node (ref "U1") (pin "117") (pinfunction "P15_8_117") (pintype "bidirectional"))
    )
    (net (code "22") (name "/CW") (class "Default")
      (node (ref "FPC3") (pin "2") (pinfunction "2_2") (pintype "unspecified"))
      (node (ref "U1") (pin "130") (pinfunction "P13_2_130") (pintype "bidirectional"))
    )
    (net (code "23") (name "/DOWN") (class "Default")
      (node (ref "U1") (pin "141") (pinfunction "P10_2_141") (pintype "bidirectional"))
    )
    (net (code "24") (name "/EN") (class "Default")
      (node (ref "SW1") (pin "2") (pinfunction "2_2") (pintype "unspecified"))
      (node (ref "U55") (pin "3") (pinfunction "EN_3") (pintype "unspecified"))
      (node (ref "U56") (pin "3") (pinfunction "EN_3") (pintype "unspecified"))
    )
    (net (code "25") (name "/EN1_ATOM2_CH6_P11_11") (class "Default")
      (node (ref "U1") (pin "138") (pinfunction "P11_11_138") (pintype "bidirectional"))
      (node (ref "U52") (pin "7") (pinfunction "7_7") (pintype "unspecified"))
    )
    (net (code "26") (name "/EN2_ATOM2_CH5_P11_10") (class "Default")
      (node (ref "U1") (pin "137") (pinfunction "P11_10_137") (pintype "bidirectional"))
      (node (ref "U52") (pin "5") (pinfunction "5_5") (pintype "unspecified"))
    )
    (net (code "27") (name "/IMU_CS") (class "Default")
      (node (ref "U1") (pin "109") (pinfunction "P15_0_109") (pintype "bidirectional"))
      (node (ref "U2") (pin "6") (pinfunction "6_6") (pintype "unspecified"))
    )
    (net (code "28") (name "/IMU_SDI") (class "Default")
      (node (ref "U1") (pin "108") (pinfunction "P20_14_108") (pintype "bidirectional"))
      (node (ref "U2") (pin "4") (pinfunction "4_4") (pintype "unspecified"))
    )
    (net (code "29") (name "/IMU_SDO") (class "Default")
      (node (ref "U1") (pin "106") (pinfunction "P20_12_106") (pintype "bidirectional"))
      (node (ref "U2") (pin "5") (pinfunction "5_5") (pintype "unspecified"))
    )
    (net (code "30") (name "/IMU_SPC") (class "Default")
      (node (ref "U1") (pin "105") (pinfunction "P20_11_105") (pintype "bidirectional"))
      (node (ref "U2") (pin "3") (pinfunction "3_3") (pintype "unspecified"))
    )
    (net (code "31") (name "/IPS_BLK") (class "Default")
      (node (ref "P1") (pin "1") (pinfunction "1_1") (pintype "input"))
      (node (ref "U1") (pin "110") (pinfunction "P15_1_110") (pintype "bidirectional"))
    )
    (net (code "32") (name "/IPS_CS") (class "Default")
      (node (ref "P1") (pin "2") (pinfunction "2_2") (pintype "input"))
      (node (ref "U1") (pin "111") (pinfunction "P15_2_111") (pintype "bidirectional"))
    )
    (net (code "33") (name "/IPS_DC") (class "Default")
      (node (ref "P1") (pin "3") (pinfunction "3_3") (pintype "input"))
      (node (ref "U1") (pin "112") (pinfunction "P15_3_112") (pintype "bidirectional"))
    )
    (net (code "34") (name "/IPS_MOSI") (class "Default")
      (node (ref "P1") (pin "5") (pinfunction "5_5") (pintype "input"))
      (node (ref "U1") (pin "114") (pinfunction "P15_5_114") (pintype "bidirectional"))
      (node (ref "U57") (pin "4") (pinfunction "4_4") (pintype "unspecified"))
    )
    (net (code "35") (name "/IPS_RST") (class "Default")
      (node (ref "P1") (pin "4") (pinfunction "4_4") (pintype "input"))
      (node (ref "U1") (pin "113") (pinfunction "P15_4_113") (pintype "bidirectional"))
    )
    (net (code "36") (name "/IPS_SCK") (class "Default")
      (node (ref "P1") (pin "6") (pinfunction "6_6") (pintype "input"))
      (node (ref "U1") (pin "115") (pinfunction "P15_6_115") (pintype "bidirectional"))
      (node (ref "U57") (pin "5") (pinfunction "5_5") (pintype "unspecified"))
    )
    (net (code "37") (name "/LFAN_ATOM3_CH2_P11_3") (class "Default")
      (node (ref "R92") (pin "2") (pinfunction "2_2") (pintype "input"))
      (node (ref "U1") (pin "133") (pinfunction "P11_3_133") (pintype "bidirectional"))
      (node (ref "U51") (pin "4") (pinfunction "B_4") (pintype "unspecified"))
    )
    (net (code "38") (name "/LFAN_PWM") (class "Default")
      (node (ref "H15") (pin "1") (pinfunction "1_1") (pintype "unspecified"))
      (node (ref "U51") (pin "3") (pinfunction "A_3") (pintype "unspecified"))
    )
    (net (code "39") (name "/LSO") (class "Default")
      (node (ref "U1") (pin "24") (pinfunction "AN49_24") (pintype "input"))
    )
    (net (code "40") (name "/M1A") (class "Default")
      (node (ref "CN9") (pin "4") (pinfunction "4_4") (pintype "unspecified"))
      (node (ref "U1") (pin "62") (pinfunction "P33_6_62") (pintype "bidirectional"))
    )
    (net (code "41") (name "/M1B") (class "Default")
      (node (ref "CN9") (pin "3") (pinfunction "3_3") (pintype "unspecified"))
      (node (ref "U1") (pin "63") (pinfunction "P33_7_63") (pintype "bidirectional"))
    )
    (net (code "42") (name "/M2A") (class "Default")
      (node (ref "CN10") (pin "4") (pinfunction "4_4") (pintype "unspecified"))
      (node (ref "U1") (pin "95") (pinfunction "P20_3_95") (pintype "bidirectional"))
    )
    (net (code "43") (name "/M2B") (class "Default")
      (node (ref "CN10") (pin "3") (pinfunction "3_3") (pintype "unspecified"))
      (node (ref "U1") (pin "93") (pinfunction "P20_0_93") (pintype "bidirectional"))
    )
    (net (code "44") (name "/P14.2") (class "Default")
      (node (ref "R71") (pin "1") (pinfunction "1_1") (pintype "input"))
      (node (ref "U1") (pin "120") (pinfunction "P14_2_120") (pintype "bidirectional"))
    )
    (net (code "45") (name "/P14.3") (class "Default")
      (node (ref "R72") (pin "1") (pinfunction "1_1") (pintype "input"))
      (node (ref "U1") (pin "121") (pinfunction "P14_3_121") (pintype "bidirectional"))
    )
    (net (code "46") (name "/P14.4") (class "Default")
      (node (ref "R75") (pin "1") (pinfunction "1_1") (pintype "input"))
      (node (ref "U1") (pin "122") (pinfunction "P14_4_122") (pintype "bidirectional"))
    )
    (net (code "47") (name "/P14.5") (class "Default")
      (node (ref "R70") (pin "1") (pinfunction "1_1") (pintype "input"))
      (node (ref "U1") (pin "123") (pinfunction "P14_5_123") (pintype "bidirectional"))
    )
    (net (code "48") (name "/P14.6") (class "Default")
      (node (ref "R69") (pin "1") (pinfunction "1_1") (pintype "input"))
      (node (ref "U1") (pin "124") (pinfunction "P14_6_124") (pintype "bidirectional"))
    )
    (net (code "49") (name "/P20.2") (class "Default")
      (node (ref "R76") (pin "1") (pinfunction "1_1") (pintype "input"))
      (node (ref "U1") (pin "94") (pinfunction "P20_2/TESTMODE_N_94") (pintype "bidirectional"))
    )
    (net (code "50") (name "/PH1_ATOM2_CH7_P11_12") (class "Default")
      (node (ref "U1") (pin "139") (pinfunction "P11_12_139") (pintype "bidirectional"))
      (node (ref "U52") (pin "6") (pinfunction "6_6") (pintype "unspecified"))
    )
    (net (code "51") (name "/PH2_ATOM2_CH4_P11_9") (class "Default")
      (node (ref "U1") (pin "135") (pinfunction "P11_9_135") (pintype "bidirectional"))
      (node (ref "U52") (pin "4") (pinfunction "4_4") (pintype "unspecified"))
    )
    (net (code "52") (name "/PRESS") (class "Default")
      (node (ref "FPC3") (pin "3") (pinfunction "3_3") (pintype "unspecified"))
      (node (ref "U1") (pin "131") (pinfunction "P13_3_131") (pintype "bidirectional"))
    )
    (net (code "53") (name "/PUSH") (class "Default")
      (node (ref "R73") (pin "1") (pinfunction "1_1") (pintype "input"))
      (node (ref "U1") (pin "143") (pinfunction "P10_5_143") (pintype "bidirectional"))
    )
    (net (code "54") (name "/PWM1") (class "Default")
      (node (ref "U1") (pin "76") (pinfunction "P22_2_76") (pintype "bidirectional"))
    )
    (net (code "55") (name "/PWM2") (class "Default")
      (node (ref "U1") (pin "77") (pinfunction "P22_3_77") (pintype "bidirectional"))
    )
    (net (code "56") (name "/RFAN_ATOM3_CH1_P11_2") (class "Default")
      (node (ref "R97") (pin "2") (pinfunction "2_2") (pintype "input"))
      (node (ref "U1") (pin "132") (pinfunction "P11_2_132") (pintype "bidirectional"))
      (node (ref "U50") (pin "4") (pinfunction "B_4") (pintype "unspecified"))
    )
    (net (code "57") (name "/RFAN_PWM") (class "Default")
      (node (ref "H15") (pin "2") (pinfunction "2_2") (pintype "unspecified"))
      (node (ref "U50") (pin "3") (pinfunction "A_3") (pintype "unspecified"))
    )
    (net (code "58") (name "/RSO") (class "Default")
      (node (ref "U1") (pin "25") (pinfunction "AN48_25") (pintype "input"))
    )
    (net (code "59") (name "/RST") (class "Default")
      (node (ref "H14") (pin "10") (pinfunction "10_10") (pintype "input"))
      (node (ref "R2") (pin "2") (pinfunction "2_2") (pintype "input"))
      (node (ref "U1") (pin "97") (pinfunction "PORST_N_97") (pintype "input"))
    )
    (net (code "60") (name "/RX") (class "Default")
      (node (ref "CN14") (pin "3") (pinfunction "3_3") (pintype "unspecified"))
      (node (ref "R49") (pin "1") (pinfunction "1_1") (pintype "input"))
      (node (ref "U1") (pin "119") (pinfunction "P14_1_119") (pintype "bidirectional"))
    )
    (net (code "61") (name "/SCL") (class "Default")
      (node (ref "U1") (pin "128") (pinfunction "P13_0_128") (pintype "bidirectional"))
    )
    (net (code "62") (name "/SDA") (class "Default")
      (node (ref "U1") (pin "129") (pinfunction "P13_1_129") (pintype "bidirectional"))
    )
    (net (code "63") (name "/SO1") (class "Default")
      (node (ref "U1") (pin "36") (pinfunction "AN24_36") (pintype "input"))
      (node (ref "U52") (pin "2") (pinfunction "2_2") (pintype "unspecified"))
    )
    (net (code "64") (name "/SO2") (class "Default")
      (node (ref "U1") (pin "35") (pinfunction "AN25_35") (pintype "input"))
      (node (ref "U52") (pin "3") (pinfunction "3_3") (pintype "unspecified"))
    )
    (net (code "65") (name "/SPI2_MISO_P15_7") (class "Default")
      (node (ref "U1") (pin "116") (pinfunction "P15_7_116") (pintype "bidirectional"))
      (node (ref "U57") (pin "6") (pinfunction "6_6") (pintype "unspecified"))
    )
    (net (code "66") (name "/STEER_PWM") (class "Default")
      (node (ref "H3") (pin "1") (pinfunction "1_1") (pintype "unspecified"))
      (node (ref "U1") (pin "68") (pinfunction "P33_12_68") (pintype "bidirectional"))
    )
    (net (code "67") (name "/TCK") (class "Default")
      (node (ref "H14") (pin "4") (pinfunction "4_4") (pintype "input"))
      (node (ref "U1") (pin "92") (pinfunction "TCK_92") (pintype "input"))
    )
    (net (code "68") (name "/TDO") (class "Default")
      (node (ref "H14") (pin "6") (pinfunction "6_6") (pintype "input"))
      (node (ref "U1") (pin "90") (pinfunction "P21_7/TDO_90") (pintype "bidirectional"))
    )
    (net (code "69") (name "/TEST") (class "Default")
      (node (ref "U1") (pin "102") (pinfunction "P20_8_102") (pintype "bidirectional"))
    )
    (net (code "70") (name "/TMS") (class "Default")
      (node (ref "H14") (pin "2") (pinfunction "2_2") (pintype "input"))
      (node (ref "U1") (pin "89") (pinfunction "TMS_89") (pintype "input"))
    )
    (net (code "71") (name "/TOFSCL") (class "Default")
      (node (ref "U1") (pin "20") (pinfunction "P00_9_20") (pintype "bidirectional"))
    )
    (net (code "72") (name "/TOFSDA") (class "Default")
      (node (ref "U1") (pin "19") (pinfunction "P00_8_19") (pintype "bidirectional"))
    )
    (net (code "73") (name "/TRST") (class "Default")
      (node (ref "H14") (pin "8") (pinfunction "8_8") (pintype "input"))
      (node (ref "R77") (pin "1") (pinfunction "1_1") (pintype "input"))
      (node (ref "U1") (pin "91") (pinfunction "TRST_N_91") (pintype "input"))
    )
    (net (code "74") (name "/TX") (class "Default")
      (node (ref "CN14") (pin "4") (pinfunction "4_4") (pintype "unspecified"))
      (node (ref "R48") (pin "1") (pinfunction "1_1") (pintype "input"))
      (node (ref "U1") (pin "118") (pinfunction "P14_0_118") (pintype "bidirectional"))
    )
    (net (code "75") (name "/TX1") (class "Default")
      (node (ref "U1") (pin "64") (pinfunction "P33_8_64") (pintype "bidirectional"))
    )
    (net (code "76") (name "/TX2") (class "Default")
      (node (ref "U1") (pin "69") (pinfunction "P33_13_69") (pintype "bidirectional"))
    )
    (net (code "77") (name "/UP") (class "Default")
      (node (ref "R74") (pin "1") (pinfunction "1_1") (pintype "input"))
      (node (ref "U1") (pin "144") (pinfunction "P10_6_144") (pintype "bidirectional"))
    )
    (net (code "78") (name "/VFB") (class "Default")
      (node (ref "R104") (pin "1") (pinfunction "1_1") (pintype "input"))
      (node (ref "R105") (pin "2") (pinfunction "2_2") (pintype "unspecified"))
      (node (ref "U55") (pin "5") (pinfunction "FB_5") (pintype "unspecified"))
    )
    (net (code "79") (name "/VFB2") (class "Default")
      (node (ref "R107") (pin "1") (pinfunction "1_1") (pintype "input"))
      (node (ref "R108") (pin "2") (pinfunction "2_2") (pintype "unspecified"))
      (node (ref "U56") (pin "5") (pinfunction "FB_5") (pintype "unspecified"))
    )
    (net (code "80") (name "/VGATE1N") (class "Default")
      (node (ref "Q1") (pin "1") (pinfunction "G1_1") (pintype "input"))
      (node (ref "U1") (pin "70") (pinfunction "P32_0/VGATE1N_70") (pintype "bidirectional"))
    )
    (net (code "81") (name "/WIFI_CS") (class "Default")
      (node (ref "U1") (pin "104") (pinfunction "P20_10_104") (pintype "bidirectional"))
      (node (ref "U57") (pin "1") (pinfunction "1_1") (pintype "unspecified"))
    )
    (net (code "82") (name "1V3") (class "Default")
      (node (ref "C10") (pin "2") (pinfunction "2_2") (pintype "input"))
      (node (ref "C24") (pin "2") (pinfunction "2_2") (pintype "input"))
      (node (ref "C4") (pin "2") (pinfunction "2_2") (pintype "input"))
      (node (ref "C5") (pin "2") (pinfunction "2_2") (pintype "input"))
      (node (ref "C6") (pin "2") (pinfunction "2_2") (pintype "input"))
      (node (ref "C7") (pin "2") (pinfunction "2_2") (pintype "input"))
      (node (ref "L1") (pin "2") (pinfunction "2_2") (pintype "input"))
      (node (ref "U1") (pin "10") (pinfunction "VDD/VDDSB_10") (pintype "input"))
      (node (ref "U1") (pin "22") (pinfunction "VDD_22") (pintype "input"))
      (node (ref "U1") (pin "58") (pinfunction "VDD_58") (pintype "input"))
      (node (ref "U1") (pin "79") (pinfunction "VDD_79") (pintype "input"))
      (node (ref "U1") (pin "99") (pinfunction "VDD_99") (pintype "input"))
    )
    (net (code "83") (name "3V3") (class "Default")
      (node (ref "C11") (pin "2") (pinfunction "2_2") (pintype "input"))
      (node (ref "C12") (pin "2") (pinfunction "2_2") (pintype "input"))
      (node (ref "C13") (pin "2") (pinfunction "2_2") (pintype "input"))
      (node (ref "C14") (pin "2") (pinfunction "2_2") (pintype "input"))
      (node (ref "C15") (pin "2") (pinfunction "2_2") (pintype "input"))
      (node (ref "C16") (pin "2") (pinfunction "2_2") (pintype "input"))
      (node (ref "C19") (pin "2") (pinfunction "2_2") (pintype "input"))
      (node (ref "C31") (pin "2") (pinfunction "2_2") (pintype "input"))
      (node (ref "C8") (pin "2") (pinfunction "2_2") (pintype "input"))
      (node (ref "C9") (pin "2") (pinfunction "2_2") (pintype "input"))
      (node (ref "CN10") (pin "2") (pinfunction "2_2") (pintype "unspecified"))
      (node (ref "CN9") (pin "2") (pinfunction "2_2") (pintype "unspecified"))
      (node (ref "D10") (pin "1") (pinfunction "K_1") (pintype "unspecified"))
      (node (ref "D8") (pin "1") (pinfunction "K_1") (pintype "unspecified"))
      (node (ref "D9") (pin "1") (pinfunction "K_1") (pintype "unspecified"))
      (node (ref "FPC3") (pin "6") (pinfunction "6_6") (pintype "unspecified"))
      (node (ref "H14") (pin "1") (pinfunction "1_1") (pintype "input"))
      (node (ref "P1") (pin "7") (pinfunction "7_7") (pintype "input"))
      (node (ref "Q1") (pin "2") (pinfunction "S2_2") (pintype "input"))
      (node (ref "R1") (pin "1") (pinfunction "1_1") (pintype "input"))
      (node (ref "R102") (pin "1") (pinfunction "1_1") (pintype "input"))
      (node (ref "R71") (pin "2") (pinfunction "2_2") (pintype "input"))
      (node (ref "R72") (pin "2") (pinfunction "2_2") (pintype "input"))
      (node (ref "R73") (pin "2") (pinfunction "2_2") (pintype "input"))
      (node (ref "R74") (pin "2") (pinfunction "2_2") (pintype "input"))
      (node (ref "R75") (pin "2") (pinfunction "2_2") (pintype "input"))
      (node (ref "R76") (pin "2") (pinfunction "2_2") (pintype "input"))
      (node (ref "R77") (pin "2") (pinfunction "2_2") (pintype "input"))
      (node (ref "R90") (pin "2") (pinfunction "2_2") (pintype "input"))
      (node (ref "U1") (pin "125") (pinfunction "VEXT_125") (pintype "input"))
      (node (ref "U1") (pin "126") (pinfunction "VDDP3_126") (pintype "input"))
      (node (ref "U1") (pin "127") (pinfunction "VDDFL3_127") (pintype "input"))
      (node (ref "U1") (pin "136") (pinfunction "VFLEX_136") (pintype "input"))
      (node (ref "U1") (pin "23") (pinfunction "VEXT_23") (pintype "input"))
      (node (ref "U1") (pin "59") (pinfunction "VEXT_59") (pintype "input"))
      (node (ref "U1") (pin "78") (pinfunction "VEXT_78") (pintype "input"))
      (node (ref "U1") (pin "83") (pinfunction "VDDP3_83") (pintype "input"))
      (node (ref "U3") (pin "5") (pinfunction "VOUT_5") (pintype "input"))
      (node (ref "U50") (pin "6") (pinfunction "VCCB_6") (pintype "unspecified"))
      (node (ref "U51") (pin "6") (pinfunction "VCCB_6") (pintype "unspecified"))
    )
    (net (code "84") (name "3V3_CSI") (class "Default")
      (node (ref "C75") (pin "2") (pinfunction "2_2") (pintype "input"))
      (node (ref "FPC1") (pin "17") (pinfunction "17_17") (pintype "unspecified"))
      (node (ref "FPC1") (pin "18") (pinfunction "18_18") (pintype "unspecified"))
      (node (ref "U54") (pin "5") (pinfunction "VOUT_5") (pintype "input"))
    )
    (net (code "85") (name "5V") (class "Default")
      (node (ref "C30") (pin "2") (pinfunction "2_2") (pintype "input"))
      (node (ref "C41") (pin "2") (pinfunction "2_2") (pintype "input"))
      (node (ref "C74") (pin "2") (pinfunction "2_2") (pintype "input"))
      (node (ref "C86") (pin "2") (pinfunction "2_2") (pintype "unspecified"))
      (node (ref "C87") (pin "2") (pinfunction "2_2") (pintype "unspecified"))
      (node (ref "CN14") (pin "1") (pinfunction "1_1") (pintype "unspecified"))
      (node (ref "L12") (pin "2") (pinfunction "2_2") (pintype "unspecified"))
      (node (ref "R107") (pin "2") (pinfunction "2_2") (pintype "input"))
      (node (ref "R47") (pin "2") (pinfunction "2_2") (pintype "input"))
      (node (ref "R96") (pin "1") (pinfunction "1_1") (pintype "input"))
      (node (ref "U2") (pin "1") (pinfunction "1_1") (pintype "unspecified"))
      (node (ref "U3") (pin "1") (pinfunction "VIN_1") (pintype "input"))
      (node (ref "U3") (pin "3") (pinfunction "CE_3") (pintype "input"))
      (node (ref "U4") (pin "1") (pinfunction "IN_1") (pintype "input"))
      (node (ref "U4") (pin "3") (pinfunction "EN_3") (pintype "input"))
      (node (ref "U50") (pin "1") (pinfunction "VCCA_1") (pintype "unspecified"))
      (node (ref "U51") (pin "1") (pinfunction "VCCA_1") (pintype "unspecified"))
      (node (ref "U54") (pin "1") (pinfunction "VIN_1") (pintype "input"))
      (node (ref "U54") (pin "3") (pinfunction "CE_3") (pintype "input"))
      (node (ref "U57") (pin "3") (pinfunction "3_3") (pintype "unspecified"))
    )
    (net (code "86") (name "12V") (class "Default")
      (node (ref "C81") (pin "2") (pinfunction "2_2") (pintype "unspecified"))
      (node (ref "C83") (pin "2") (pinfunction "2_2") (pintype "unspecified"))
      (node (ref "C84") (pin "2") (pinfunction "2_2") (pintype "unspecified"))
      (node (ref "C88") (pin "2") (pinfunction "2_2") (pintype "unspecified"))
      (node (ref "C90") (pin "2") (pinfunction "2_2") (pintype "unspecified"))
      (node (ref "C91") (pin "2") (pinfunction "2_2") (pintype "unspecified"))
      (node (ref "SW1") (pin "1") (pinfunction "1_1") (pintype "unspecified"))
      (node (ref "U55") (pin "2") (pinfunction "VIN_2") (pintype "unspecified"))
      (node (ref "U56") (pin "2") (pinfunction "VIN_2") (pintype "unspecified"))
      (node (ref "U58") (pin "2") (pinfunction "2_2") (pintype "unspecified"))
    )
    (net (code "87") (name "AGND") (class "Default")
      (node (ref "C42") (pin "1") (pinfunction "1_1") (pintype "input"))
      (node (ref "C43") (pin "1") (pinfunction "1_1") (pintype "input"))
      (node (ref "R112") (pin "2") (pinfunction "2_2") (pintype "input"))
      (node (ref "U1") (pin "41") (pinfunction "VAGND1_41") (pintype "input"))
      (node (ref "U1") (pin "43") (pinfunction "VSSM_43") (pintype "input"))
    )
    (net (code "88") (name "AVCC") (class "Default")
      (node (ref "C42") (pin "2") (pinfunction "2_2") (pintype "input"))
      (node (ref "C43") (pin "2") (pinfunction "2_2") (pintype "input"))
      (node (ref "U1") (pin "42") (pinfunction "VAREF1_42") (pintype "input"))
      (node (ref "U1") (pin "44") (pinfunction "VDDM_44") (pintype "input"))
      (node (ref "U4") (pin "5") (pinfunction "OUT_5") (pintype "input"))
    )
    (net (code "89") (name "GND") (class "Default")
      (node (ref "C10") (pin "1") (pinfunction "1_1") (pintype "input"))
      (node (ref "C11") (pin "1") (pinfunction "1_1") (pintype "input"))
      (node (ref "C12") (pin "1") (pinfunction "1_1") (pintype "input"))
      (node (ref "C13") (pin "1") (pinfunction "1_1") (pintype "input"))
      (node (ref "C14") (pin "1") (pinfunction "1_1") (pintype "input"))
      (node (ref "C15") (pin "1") (pinfunction "1_1") (pintype "input"))
      (node (ref "C16") (pin "1") (pinfunction "1_1") (pintype "input"))
      (node (ref "C19") (pin "1") (pinfunction "1_1") (pintype "input"))
      (node (ref "C24") (pin "1") (pinfunction "1_1") (pintype "input"))
      (node (ref "C3") (pin "1") (pinfunction "1_1") (pintype "input"))
      (node (ref "C30") (pin "1") (pinfunction "1_1") (pintype "input"))
      (node (ref "C31") (pin "1") (pinfunction "1_1") (pintype "input"))
      (node (ref "C4") (pin "1") (pinfunction "1_1") (pintype "input"))
      (node (ref "C41") (pin "1") (pinfunction "1_1") (pintype "input"))
      (node (ref "C5") (pin "1") (pinfunction "1_1") (pintype "input"))
      (node (ref "C6") (pin "1") (pinfunction "1_1") (pintype "input"))
      (node (ref "C7") (pin "1") (pinfunction "1_1") (pintype "input"))
      (node (ref "C74") (pin "1") (pinfunction "1_1") (pintype "input"))
      (node (ref "C75") (pin "1") (pinfunction "1_1") (pintype "input"))
      (node (ref "C8") (pin "1") (pinfunction "1_1") (pintype "input"))
      (node (ref "C86") (pin "1") (pinfunction "1_1") (pintype "unspecified"))
      (node (ref "C87") (pin "1") (pinfunction "1_1") (pintype "unspecified"))
      (node (ref "C88") (pin "1") (pinfunction "1_1") (pintype "unspecified"))
      (node (ref "C89") (pin "2") (pinfunction "2_2") (pintype "input"))
      (node (ref "C9") (pin "1") (pinfunction "1_1") (pintype "input"))
      (node (ref "C90") (pin "1") (pinfunction "1_1") (pintype "unspecified"))
      (node (ref "C91") (pin "1") (pinfunction "1_1") (pintype "unspecified"))
      (node (ref "CN10") (pin "1") (pinfunction "1_1") (pintype "unspecified"))
      (node (ref "CN14") (pin "2") (pinfunction "2_2") (pintype "unspecified"))
      (node (ref "CN14") (pin "5") (pinfunction "5_5") (pintype "unspecified"))
      (node (ref "CN14") (pin "6") (pinfunction "6_6") (pintype "unspecified"))
      (node (ref "CN9") (pin "1") (pinfunction "1_1") (pintype "unspecified"))
      (node (ref "D10") (pin "2") (pinfunction "A_2") (pintype "unspecified"))
      (node (ref "D12") (pin "1") (pinfunction "A_1") (pintype "unspecified"))
      (node (ref "D8") (pin "2") (pinfunction "A_2") (pintype "unspecified"))
      (node (ref "D9") (pin "2") (pinfunction "A_2") (pintype "unspecified"))
      (node (ref "FPC1") (pin "16") (pinfunction "16_16") (pintype "unspecified"))
      (node (ref "FPC1") (pin "19") (pinfunction "19_19") (pintype "unspecified"))
      (node (ref "FPC1") (pin "2") (pinfunction "2_2") (pintype "unspecified"))
      (node (ref "FPC1") (pin "20") (pinfunction "20_20") (pintype "unspecified"))
      (node (ref "FPC1") (pin "7") (pinfunction "7_7") (pintype "unspecified"))
      (node (ref "FPC3") (pin "4") (pinfunction "4_4") (pintype "unspecified"))
      (node (ref "FPC3") (pin "5") (pinfunction "5_5") (pintype "unspecified"))
      (node (ref "FPC3") (pin "7") (pinfunction "7_7") (pintype "unspecified"))
      (node (ref "FPC3") (pin "8") (pinfunction "8_8") (pintype "unspecified"))
      (node (ref "H14") (pin "3") (pinfunction "3_3") (pintype "input"))
      (node (ref "H14") (pin "5") (pinfunction "5_5") (pintype "input"))
      (node (ref "H15") (pin "5") (pinfunction "5_5") (pintype "unspecified"))
      (node (ref "H15") (pin "6") (pinfunction "6_6") (pintype "unspecified"))
      (node (ref "LED14") (pin "1") (pinfunction "K_1") (pintype "input"))
      (node (ref "LED15") (pin "1") (pinfunction "K_1") (pintype "input"))
      (node (ref "P1") (pin "8") (pinfunction "8_8") (pintype "input"))
      (node (ref "Q1") (pin "5") (pinfunction "S1_5") (pintype "input"))
      (node (ref "Q9") (pin "2") (pinfunction "E_2") (pintype "unspecified"))
      (node (ref "R106") (pin "1") (pinfunction "1_1") (pintype "unspecified"))
      (node (ref "R108") (pin "1") (pinfunction "1_1") (pintype "unspecified"))
      (node (ref "R109") (pin "1") (pinfunction "1_1") (pintype "input"))
      (node (ref "R110") (pin "1") (pinfunction "1_1") (pintype "unspecified"))
      (node (ref "R111") (pin "1") (pinfunction "1_1") (pintype "unspecified"))
      (node (ref "R112") (pin "1") (pinfunction "1_1") (pintype "input"))
      (node (ref "R69") (pin "2") (pinfunction "2_2") (pintype "input"))
      (node (ref "R70") (pin "2") (pinfunction "2_2") (pintype "input"))
      (node (ref "R92") (pin "1") (pinfunction "1_1") (pintype "input"))
      (node (ref "R97") (pin "1") (pinfunction "1_1") (pintype "input"))
      (node (ref "SW2") (pin "2") (pinfunction "2_2") (pintype "input"))
      (node (ref "U1") (pin "145") (pinfunction "EP_145") (pintype "input"))
      (node (ref "U1") (pin "80") (pinfunction "VSS_80") (pintype "input"))
      (node (ref "U2") (pin "2") (pinfunction "2_2") (pintype "unspecified"))
      (node (ref "U2") (pin "7") (pinfunction "7_7") (pintype "unspecified"))
      (node (ref "U2") (pin "8") (pinfunction "8_8") (pintype "unspecified"))
      (node (ref "U3") (pin "2") (pinfunction "VSS_2") (pintype "input"))
      (node (ref "U4") (pin "2") (pinfunction "GND_2") (pintype "input"))
      (node (ref "U50") (pin "2") (pinfunction "GND_2") (pintype "unspecified"))
      (node (ref "U50") (pin "5") (pinfunction "DIR_5") (pintype "unspecified"))
      (node (ref "U51") (pin "2") (pinfunction "GND_2") (pintype "unspecified"))
      (node (ref "U51") (pin "5") (pinfunction "DIR_5") (pintype "unspecified"))
      (node (ref "U52") (pin "1") (pinfunction "1_1") (pintype "unspecified"))
      (node (ref "U52") (pin "10") (pinfunction "10_10") (pintype "unspecified"))
      (node (ref "U52") (pin "11") (pinfunction "11_11") (pintype "unspecified"))
      (node (ref "U52") (pin "8") (pinfunction "8_8") (pintype "unspecified"))
      (node (ref "U54") (pin "2") (pinfunction "VSS_2") (pintype "input"))
      (node (ref "U56") (pin "7") (pinfunction "GND_7") (pintype "unspecified"))
      (node (ref "U56") (pin "9") (pinfunction "EPAD_9") (pintype "unspecified"))
      (node (ref "U57") (pin "2") (pinfunction "2_2") (pintype "unspecified"))
      (node (ref "U57") (pin "7") (pinfunction "7_7") (pintype "unspecified"))
      (node (ref "U57") (pin "8") (pinfunction "8_8") (pintype "unspecified"))
      (node (ref "X3") (pin "2") (pinfunction "GND_2") (pintype "input"))
    )
    (net (code "90") (name "Net-(BUZZER2-Pad1)") (class "Default")
      (node (ref "BUZZER2") (pin "1") (pinfunction "1_1") (pintype "unspecified"))
      (node (ref "R102") (pin "2") (pinfunction "2_2") (pintype "input"))
    )
    (net (code "91") (name "Net-(C3-Pad2)") (class "Default")
      (node (ref "C3") (pin "2") (pinfunction "2_2") (pintype "input"))
      (node (ref "R1") (pin "2") (pinfunction "2_2") (pintype "input"))
      (node (ref "R2") (pin "1") (pinfunction "1_1") (pintype "input"))
      (node (ref "SW2") (pin "1") (pinfunction "1_1") (pintype "input"))
    )
    (net (code "92") (name "Net-(D11-K)") (class "Default")
      (node (ref "C78") (pin "2") (pinfunction "2_2") (pintype "unspecified"))
      (node (ref "D11") (pin "2") (pinfunction "K_2") (pintype "unspecified"))
      (node (ref "L13") (pin "1") (pinfunction "1_1") (pintype "unspecified"))
      (node (ref "U55") (pin "8") (pinfunction "SW_8") (pintype "unspecified"))
    )
    (net (code "93") (name "Net-(D12-K)") (class "Default")
      (node (ref "C85") (pin "2") (pinfunction "2_2") (pintype "unspecified"))
      (node (ref "D12") (pin "2") (pinfunction "K_2") (pintype "unspecified"))
      (node (ref "L12") (pin "1") (pinfunction "1_1") (pintype "unspecified"))
      (node (ref "U56") (pin "8") (pinfunction "SW_8") (pintype "unspecified"))
    )
    (net (code "94") (name "Net-(H14-Pad7)") (class "Default")
      (node (ref "H14") (pin "7") (pinfunction "7_7") (pintype "input"))
      (node (ref "R48") (pin "2") (pinfunction "2_2") (pintype "input"))
    )
    (net (code "95") (name "Net-(H14-Pad9)") (class "Default")
      (node (ref "H14") (pin "9") (pinfunction "9_9") (pintype "input"))
      (node (ref "R49") (pin "2") (pinfunction "2_2") (pintype "input"))
    )
    (net (code "96") (name "Net-(H15-Pad3)") (class "Default")
      (node (ref "H15") (pin "3") (pinfunction "3_3") (pintype "unspecified"))
      (node (ref "H15") (pin "4") (pinfunction "4_4") (pintype "unspecified"))
      (node (ref "R96") (pin "2") (pinfunction "2_2") (pintype "input"))
    )
    (net (code "97") (name "Net-(LED14-A)") (class "Default")
      (node (ref "LED14") (pin "2") (pinfunction "A_2") (pintype "input"))
      (node (ref "R90") (pin "1") (pinfunction "1_1") (pintype "input"))
    )
    (net (code "98") (name "Net-(LED15-A)") (class "Default")
      (node (ref "LED15") (pin "2") (pinfunction "A_2") (pintype "input"))
      (node (ref "R47") (pin "1") (pinfunction "1_1") (pintype "input"))
    )
    (net (code "99") (name "Net-(LED16-+)") (class "Default")
      (node (ref "LED16") (pin "2") (pinfunction "+_2") (pintype "input"))
      (node (ref "R93") (pin "2") (pinfunction "2_2") (pintype "input"))
    )
    (net (code "100") (name "Net-(Q1-D1)") (class "Default")
      (node (ref "L1") (pin "1") (pinfunction "1_1") (pintype "input"))
      (node (ref "Q1") (pin "4") (pinfunction "D2_4") (pintype "input"))
      (node (ref "Q1") (pin "6") (pinfunction "D1_6") (pintype "input"))
    )
    (net (code "101") (name "Net-(Q1-G2)") (class "Default")
      (node (ref "Q1") (pin "3") (pinfunction "G2_3") (pintype "input"))
      (node (ref "U1") (pin "71") (pinfunction "VGATE1P_71") (pintype "output"))
    )
    (net (code "102") (name "Net-(Q9-B)") (class "Default")
      (node (ref "Q9") (pin "1") (pinfunction "B_1") (pintype "unspecified"))
      (node (ref "R14") (pin "2") (pinfunction "2_2") (pintype "input"))
    )
    (net (code "103") (name "Net-(Q9-C)") (class "Default")
      (node (ref "BUZZER2") (pin "2") (pinfunction "2_2") (pintype "unspecified"))
      (node (ref "Q9") (pin "3") (pinfunction "C_3") (pintype "unspecified"))
    )
    (net (code "104") (name "Net-(U1A-XTAL1)") (class "Default")
      (node (ref "U1") (pin "81") (pinfunction "XTAL1_81") (pintype "input"))
      (node (ref "X3") (pin "1") (pinfunction "OSC1_1") (pintype "input"))
    )
    (net (code "105") (name "Net-(U1A-XTAL2)") (class "Default")
      (node (ref "U1") (pin "82") (pinfunction "XTAL2_82") (pintype "output"))
      (node (ref "X3") (pin "3") (pinfunction "OSC2_3") (pintype "input"))
    )
    (net (code "106") (name "Net-(U55-BOOT)") (class "Default")
      (node (ref "C78") (pin "1") (pinfunction "1_1") (pintype "unspecified"))
      (node (ref "U55") (pin "1") (pinfunction "BOOT_1") (pintype "unspecified"))
    )
    (net (code "107") (name "Net-(U55-RT{slash}SYNC)") (class "Default")
      (node (ref "R103") (pin "2") (pinfunction "2_2") (pintype "unspecified"))
      (node (ref "U55") (pin "4") (pinfunction "RT/SYNC_4") (pintype "unspecified"))
    )
    (net (code "108") (name "Net-(U55-SS)") (class "Default")
      (node (ref "C82") (pin "1") (pinfunction "1_1") (pintype "input"))
      (node (ref "U55") (pin "6") (pinfunction "SS_6") (pintype "unspecified"))
    )
    (net (code "109") (name "Net-(U56-BOOT)") (class "Default")
      (node (ref "C85") (pin "1") (pinfunction "1_1") (pintype "unspecified"))
      (node (ref "U56") (pin "1") (pinfunction "BOOT_1") (pintype "unspecified"))
    )
    (net (code "110") (name "Net-(U56-RT{slash}SYNC)") (class "Default")
      (node (ref "R106") (pin "2") (pinfunction "2_2") (pintype "unspecified"))
      (node (ref "U56") (pin "4") (pinfunction "RT/SYNC_4") (pintype "unspecified"))
    )
    (net (code "111") (name "Net-(U56-SS)") (class "Default")
      (node (ref "C89") (pin "1") (pinfunction "1_1") (pintype "input"))
      (node (ref "U56") (pin "6") (pinfunction "SS_6") (pintype "unspecified"))
    )
    (net (code "112") (name "PGND") (class "Default")
      (node (ref "C79") (pin "1") (pinfunction "1_1") (pintype "unspecified"))
      (node (ref "C80") (pin "1") (pinfunction "1_1") (pintype "unspecified"))
      (node (ref "C81") (pin "1") (pinfunction "1_1") (pintype "unspecified"))
      (node (ref "C82") (pin "2") (pinfunction "2_2") (pintype "input"))
      (node (ref "C83") (pin "1") (pinfunction "1_1") (pintype "unspecified"))
      (node (ref "C84") (pin "1") (pinfunction "1_1") (pintype "unspecified"))
      (node (ref "D11") (pin "1") (pinfunction "A_1") (pintype "unspecified"))
      (node (ref "H3") (pin "3") (pinfunction "3_3") (pintype "unspecified"))
      (node (ref "LED16") (pin "1") (pinfunction "-_1") (pintype "input"))
      (node (ref "R103") (pin "1") (pinfunction "1_1") (pintype "unspecified"))
      (node (ref "R105") (pin "1") (pinfunction "1_1") (pintype "unspecified"))
      (node (ref "R109") (pin "2") (pinfunction "2_2") (pintype "input"))
      (node (ref "R110") (pin "2") (pinfunction "2_2") (pintype "unspecified"))
      (node (ref "R111") (pin "2") (pinfunction "2_2") (pintype "unspecified"))
      (node (ref "SW1") (pin "3") (pinfunction "3_3") (pintype "unspecified"))
      (node (ref "SW1") (pin "4") (pinfunction "4_4") (pintype "unspecified"))
      (node (ref "U55") (pin "7") (pinfunction "GND_7") (pintype "unspecified"))
      (node (ref "U55") (pin "9") (pinfunction "EPAD_9") (pintype "unspecified"))
      (node (ref "U58") (pin "1") (pinfunction "1_1") (pintype "unspecified"))
    )
    (net (code "113") (name "unconnected-(CN9-Pad5)") (class "Default")
      (node (ref "CN9") (pin "5") (pinfunction "5_5") (pintype "unspecified"))
    )
    (net (code "114") (name "unconnected-(CN9-Pad6)") (class "Default")
      (node (ref "CN9") (pin "6") (pinfunction "6_6") (pintype "unspecified"))
    )
    (net (code "115") (name "unconnected-(CN10-Pad5)") (class "Default")
      (node (ref "CN10") (pin "5") (pinfunction "5_5") (pintype "unspecified"))
    )
    (net (code "116") (name "unconnected-(CN10-Pad6)") (class "Default")
      (node (ref "CN10") (pin "6") (pinfunction "6_6") (pintype "unspecified"))
    )
    (net (code "117") (name "unconnected-(FPC1-Pad5)") (class "Default")
      (node (ref "FPC1") (pin "5") (pinfunction "5_5") (pintype "unspecified"))
    )
    (net (code "118") (name "unconnected-(U1A-ESR0_N-Pad98)") (class "Default")
      (node (ref "U1") (pin "98") (pinfunction "ESR0_N_98") (pintype "bidirectional"))
    )
    (net (code "119") (name "unconnected-(U1A-ESR1_N-Pad96)") (class "Default")
      (node (ref "U1") (pin "96") (pinfunction "ESR1_N_96") (pintype "bidirectional"))
    )
    (net (code "120") (name "unconnected-(U1B-AN0-Pad57)") (class "Default")
      (node (ref "U1") (pin "57") (pinfunction "AN0_57") (pintype "input"))
    )
    (net (code "121") (name "unconnected-(U1B-AN1-Pad56)") (class "Default")
      (node (ref "U1") (pin "56") (pinfunction "AN1_56") (pintype "input"))
    )
    (net (code "122") (name "unconnected-(U1B-AN2-Pad55)") (class "Default")
      (node (ref "U1") (pin "55") (pinfunction "AN2_55") (pintype "input"))
    )
    (net (code "123") (name "unconnected-(U1B-AN3-Pad54)") (class "Default")
      (node (ref "U1") (pin "54") (pinfunction "AN3_54") (pintype "input"))
    )
    (net (code "124") (name "unconnected-(U1B-AN5-Pad52)") (class "Default")
      (node (ref "U1") (pin "52") (pinfunction "AN5_52") (pintype "input"))
    )
    (net (code "125") (name "unconnected-(U1B-AN6-Pad51)") (class "Default")
      (node (ref "U1") (pin "51") (pinfunction "AN6_51") (pintype "input"))
    )
    (net (code "126") (name "unconnected-(U1B-AN7-Pad50)") (class "Default")
      (node (ref "U1") (pin "50") (pinfunction "AN7_50") (pintype "input"))
    )
    (net (code "127") (name "unconnected-(U1B-AN8-Pad49)") (class "Default")
      (node (ref "U1") (pin "49") (pinfunction "AN8_49") (pintype "input"))
    )
    (net (code "128") (name "unconnected-(U1B-AN10-Pad48)") (class "Default")
      (node (ref "U1") (pin "48") (pinfunction "AN10_48") (pintype "input"))
    )
    (net (code "129") (name "unconnected-(U1B-AN11-Pad47)") (class "Default")
      (node (ref "U1") (pin "47") (pinfunction "AN11_47") (pintype "input"))
    )
    (net (code "130") (name "unconnected-(U1B-AN12-Pad46)") (class "Default")
      (node (ref "U1") (pin "46") (pinfunction "AN12_46") (pintype "input"))
    )
    (net (code "131") (name "unconnected-(U1B-AN13-Pad45)") (class "Default")
      (node (ref "U1") (pin "45") (pinfunction "AN13_45") (pintype "input"))
    )
    (net (code "132") (name "unconnected-(U1B-AN35-Pad34)") (class "Default")
      (node (ref "U1") (pin "34") (pinfunction "AN35_34") (pintype "input"))
    )
    (net (code "133") (name "unconnected-(U1B-AN36-Pad33)") (class "Default")
      (node (ref "U1") (pin "33") (pinfunction "AN36_33") (pintype "input"))
    )
    (net (code "134") (name "unconnected-(U1B-AN37-Pad32)") (class "Default")
      (node (ref "U1") (pin "32") (pinfunction "AN37_32") (pintype "input"))
    )
    (net (code "135") (name "unconnected-(U1B-AN38-Pad31)") (class "Default")
      (node (ref "U1") (pin "31") (pinfunction "AN38_31") (pintype "input"))
    )
    (net (code "136") (name "unconnected-(U1B-AN39-Pad30)") (class "Default")
      (node (ref "U1") (pin "30") (pinfunction "AN39_30") (pintype "input"))
    )
    (net (code "137") (name "unconnected-(U1B-AN44-Pad29)") (class "Default")
      (node (ref "U1") (pin "29") (pinfunction "AN44_29") (pintype "input"))
    )
    (net (code "138") (name "unconnected-(U1B-AN45-Pad28)") (class "Default")
      (node (ref "U1") (pin "28") (pinfunction "AN45_28") (pintype "input"))
    )
    (net (code "139") (name "unconnected-(U1B-AN46-Pad27)") (class "Default")
      (node (ref "U1") (pin "27") (pinfunction "AN46_27") (pintype "input"))
    )
    (net (code "140") (name "unconnected-(U1B-AN47-Pad26)") (class "Default")
      (node (ref "U1") (pin "26") (pinfunction "AN47_26") (pintype "input"))
    )
    (net (code "141") (name "unconnected-(U1C-P20_6-Pad100)") (class "Default")
      (node (ref "U1") (pin "100") (pinfunction "P20_6_100") (pintype "bidirectional"))
    )
    (net (code "142") (name "unconnected-(U1C-P20_7-Pad101)") (class "Default")
      (node (ref "U1") (pin "101") (pinfunction "P20_7_101") (pintype "bidirectional"))
    )
    (net (code "143") (name "unconnected-(U1C-P20_13-Pad107)") (class "Default")
      (node (ref "U1") (pin "107") (pinfunction "P20_13_107") (pintype "bidirectional"))
    )
    (net (code "144") (name "unconnected-(U1C-P21_2-Pad84)") (class "Default")
      (node (ref "U1") (pin "84") (pinfunction "P21_2_84") (pintype "bidirectional"))
    )
    (net (code "145") (name "unconnected-(U1C-P21_3-Pad85)") (class "Default")
      (node (ref "U1") (pin "85") (pinfunction "P21_3_85") (pintype "bidirectional"))
    )
    (net (code "146") (name "unconnected-(U1C-P21_4-Pad86)") (class "Default")
      (node (ref "U1") (pin "86") (pinfunction "P21_4_86") (pintype "bidirectional"))
    )
    (net (code "147") (name "unconnected-(U1C-P21_5-Pad87)") (class "Default")
      (node (ref "U1") (pin "87") (pinfunction "P21_5_87") (pintype "bidirectional"))
    )
    (net (code "148") (name "unconnected-(U1C-P21_6{slash}TDI-Pad88)") (class "Default")
      (node (ref "U1") (pin "88") (pinfunction "P21_6/TDI_88") (pintype "bidirectional"))
    )
    (net (code "149") (name "unconnected-(U1C-P22_0-Pad74)") (class "Default")
      (node (ref "U1") (pin "74") (pinfunction "P22_0_74") (pintype "bidirectional"))
    )
    (net (code "150") (name "unconnected-(U1C-P22_1-Pad75)") (class "Default")
      (node (ref "U1") (pin "75") (pinfunction "P22_1_75") (pintype "bidirectional"))
    )
    (net (code "151") (name "unconnected-(U1C-P23_1-Pad73)") (class "Default")
      (node (ref "U1") (pin "73") (pinfunction "P23_1_73") (pintype "bidirectional"))
    )
    (net (code "152") (name "unconnected-(U1C-P32_4-Pad72)") (class "Default")
      (node (ref "U1") (pin "72") (pinfunction "P32_4_72") (pintype "bidirectional"))
    )
    (net (code "153") (name "unconnected-(U1C-P33_4-Pad60)") (class "Default")
      (node (ref "U1") (pin "60") (pinfunction "P33_4_60") (pintype "bidirectional"))
    )
    (net (code "154") (name "unconnected-(U1C-P33_5-Pad61)") (class "Default")
      (node (ref "U1") (pin "61") (pinfunction "P33_5_61") (pintype "bidirectional"))
    )
    (net (code "155") (name "unconnected-(U1C-P33_9-Pad65)") (class "Default")
      (node (ref "U1") (pin "65") (pinfunction "P33_9_65") (pintype "bidirectional"))
    )
    (net (code "156") (name "unconnected-(U1C-P33_11-Pad67)") (class "Default")
      (node (ref "U1") (pin "67") (pinfunction "P33_11_67") (pintype "bidirectional"))
    )
    (net (code "157") (name "unconnected-(U1D-P00_12-Pad21)") (class "Default")
      (node (ref "U1") (pin "21") (pinfunction "P00_12_21") (pintype "bidirectional"))
    )
    (net (code "158") (name "unconnected-(U1D-P02_4-Pad5)") (class "Default")
      (node (ref "U1") (pin "5") (pinfunction "P02_4_5") (pintype "bidirectional"))
    )
    (net (code "159") (name "unconnected-(U1D-P02_5-Pad6)") (class "Default")
      (node (ref "U1") (pin "6") (pinfunction "P02_5_6") (pintype "bidirectional"))
    )
    (net (code "160") (name "unconnected-(U1D-P02_6-Pad7)") (class "Default")
      (node (ref "U1") (pin "7") (pinfunction "P02_6_7") (pintype "bidirectional"))
    )
    (net (code "161") (name "unconnected-(U1D-P02_7-Pad8)") (class "Default")
      (node (ref "U1") (pin "8") (pinfunction "P02_7_8") (pintype "bidirectional"))
    )
    (net (code "162") (name "unconnected-(U1D-P02_8-Pad9)") (class "Default")
      (node (ref "U1") (pin "9") (pinfunction "P02_8_9") (pintype "bidirectional"))
    )
    (net (code "163") (name "unconnected-(U1D-P10_1-Pad140)") (class "Default")
      (node (ref "U1") (pin "140") (pinfunction "P10_1_140") (pintype "bidirectional"))
    )
    (net (code "164") (name "unconnected-(U1D-P10_3-Pad142)") (class "Default")
      (node (ref "U1") (pin "142") (pinfunction "P10_3_142") (pintype "bidirectional"))
    )
    (net (code "165") (name "unconnected-(U1D-P11_6-Pad134)") (class "Default")
      (node (ref "U1") (pin "134") (pinfunction "P11_6_134") (pintype "bidirectional"))
    )
    (net (code "166") (name "unconnected-(U3-NC-Pad4)") (class "Default")
      (node (ref "U3") (pin "4") (pinfunction "NC_4") (pintype "input"))
    )
    (net (code "167") (name "unconnected-(U4-NC-Pad4)") (class "Default")
      (node (ref "U4") (pin "4") (pinfunction "NC_4") (pintype "input"))
    )
    (net (code "168") (name "unconnected-(U54-NC-Pad4)") (class "Default")
      (node (ref "U54") (pin "4") (pinfunction "NC_4") (pintype "input"))
    )
  )
)
